# rev_m_v4.net
KiCad netlist of a schematic drawn in EAGLE
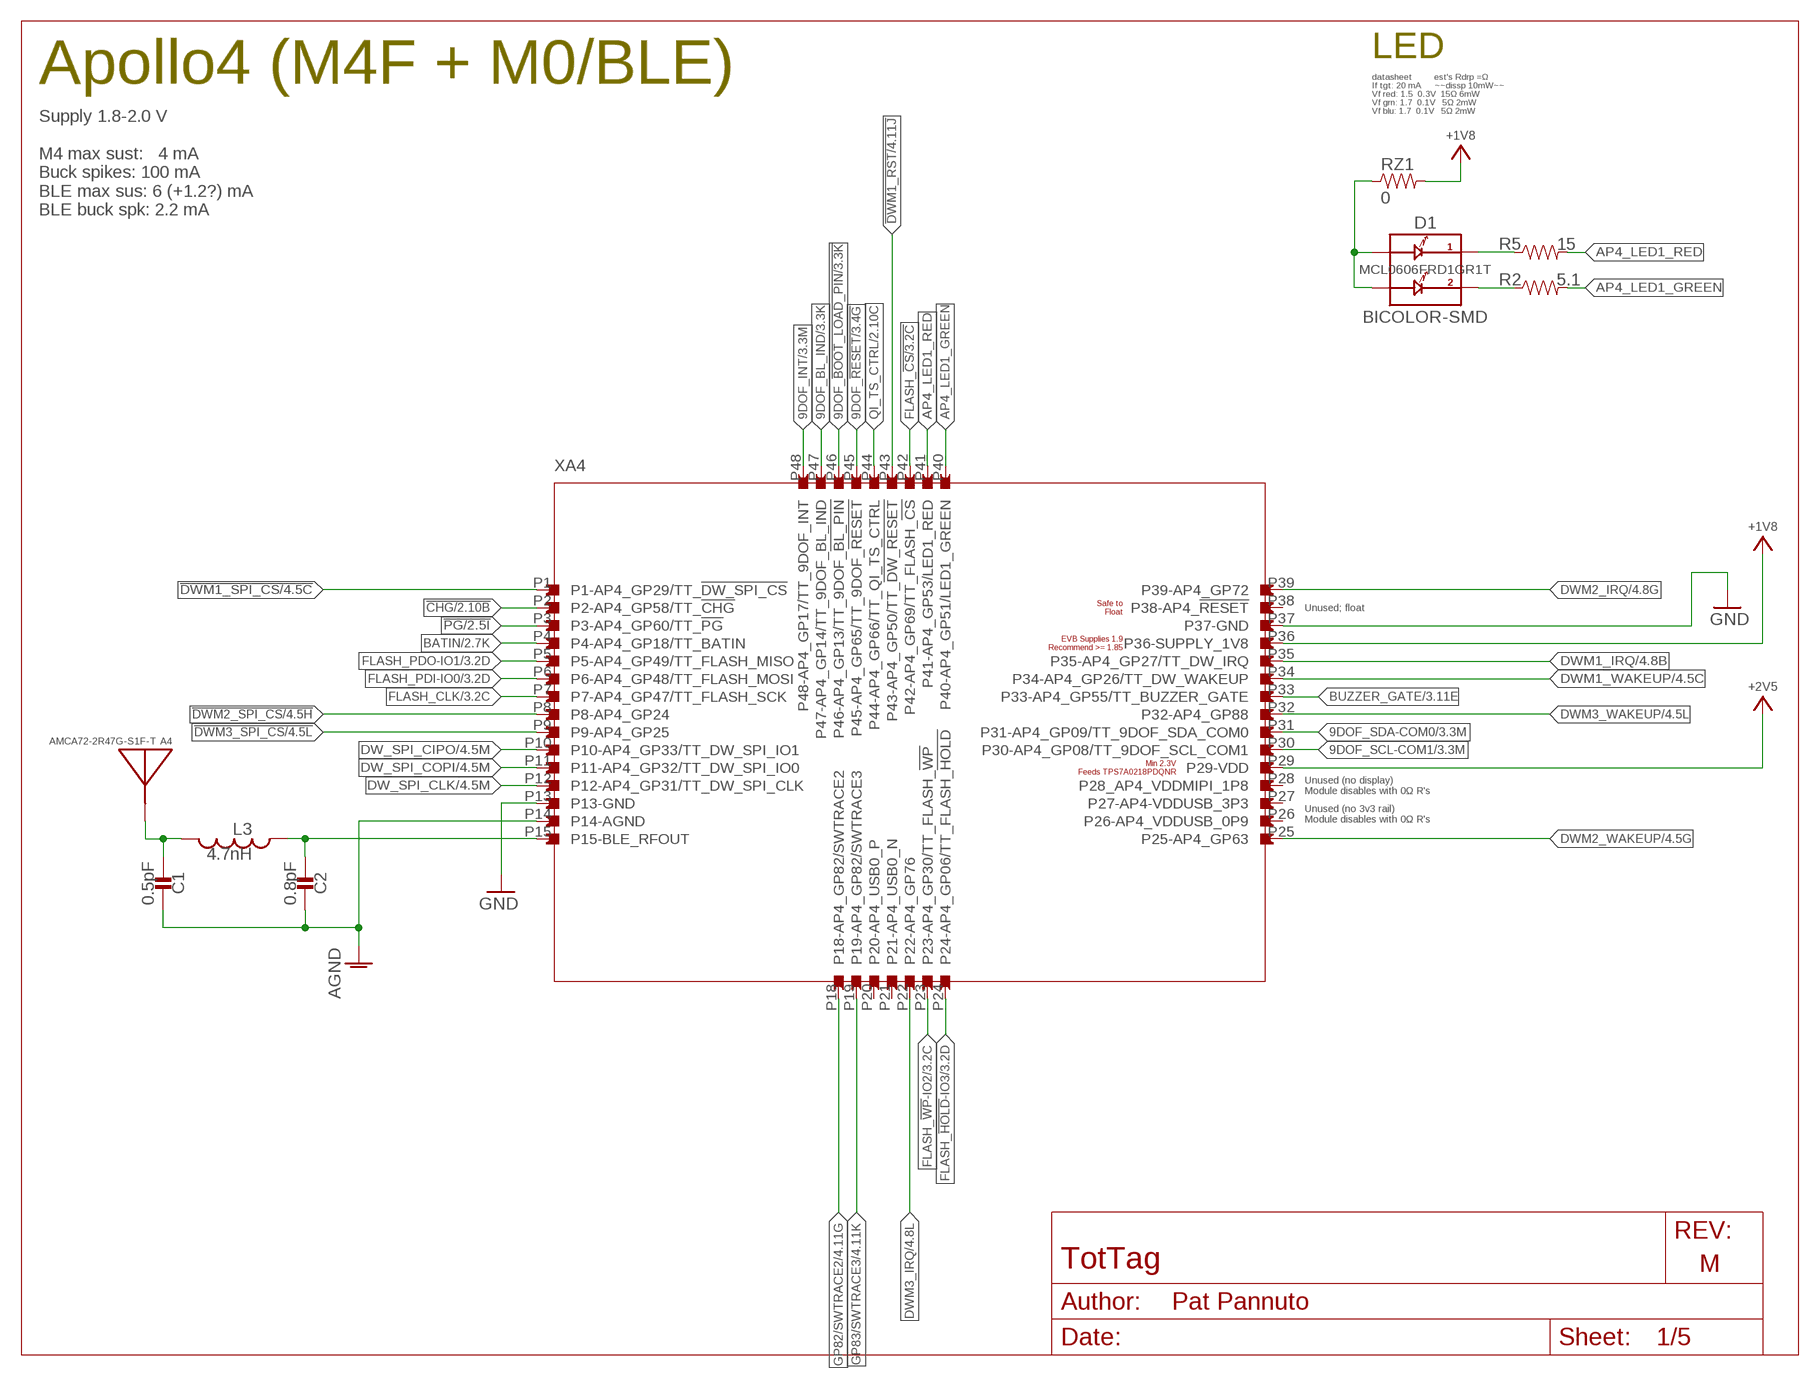
[diagram p0: schematic, sheet 1]
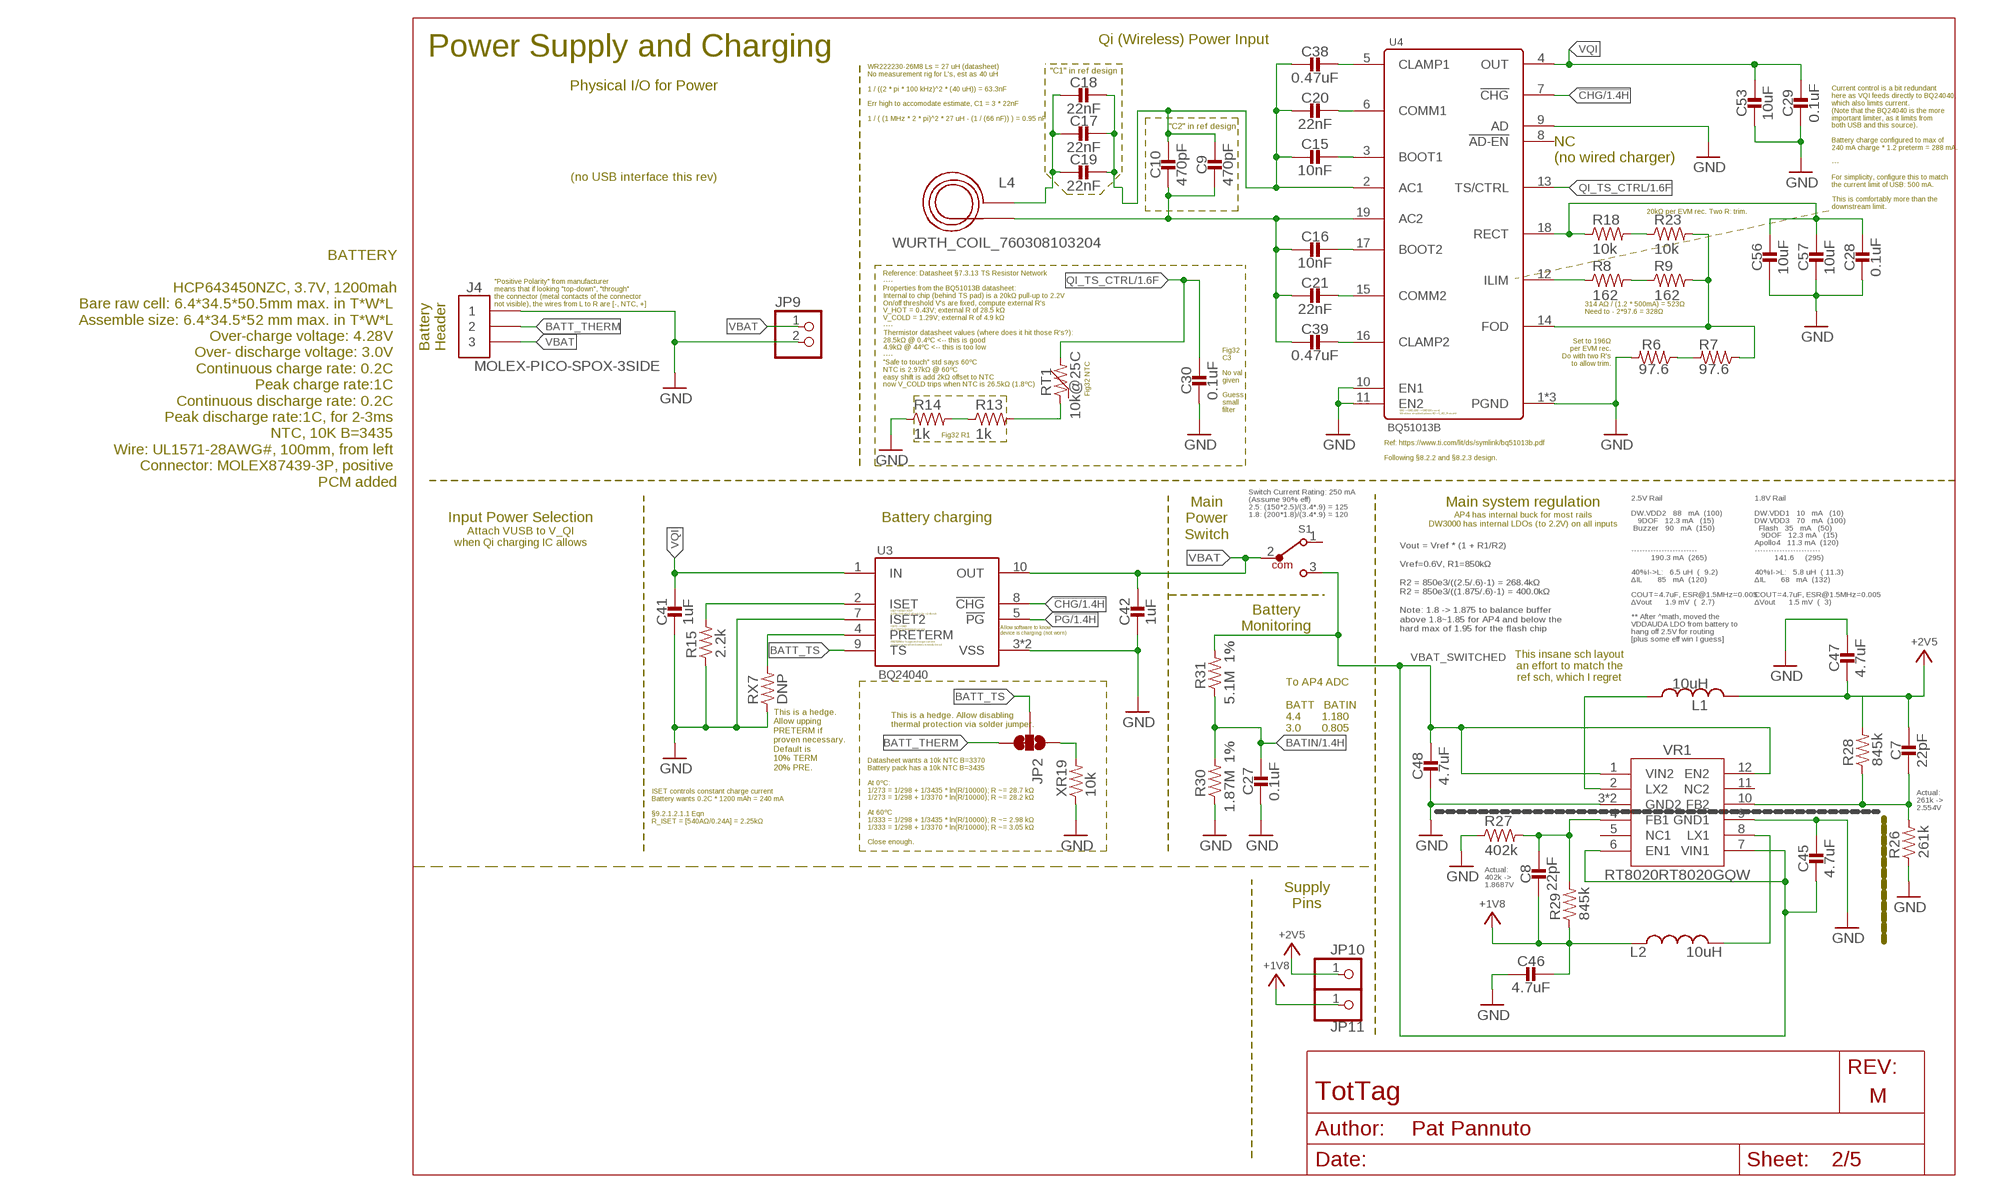
[diagram p1: schematic, sheet 2]
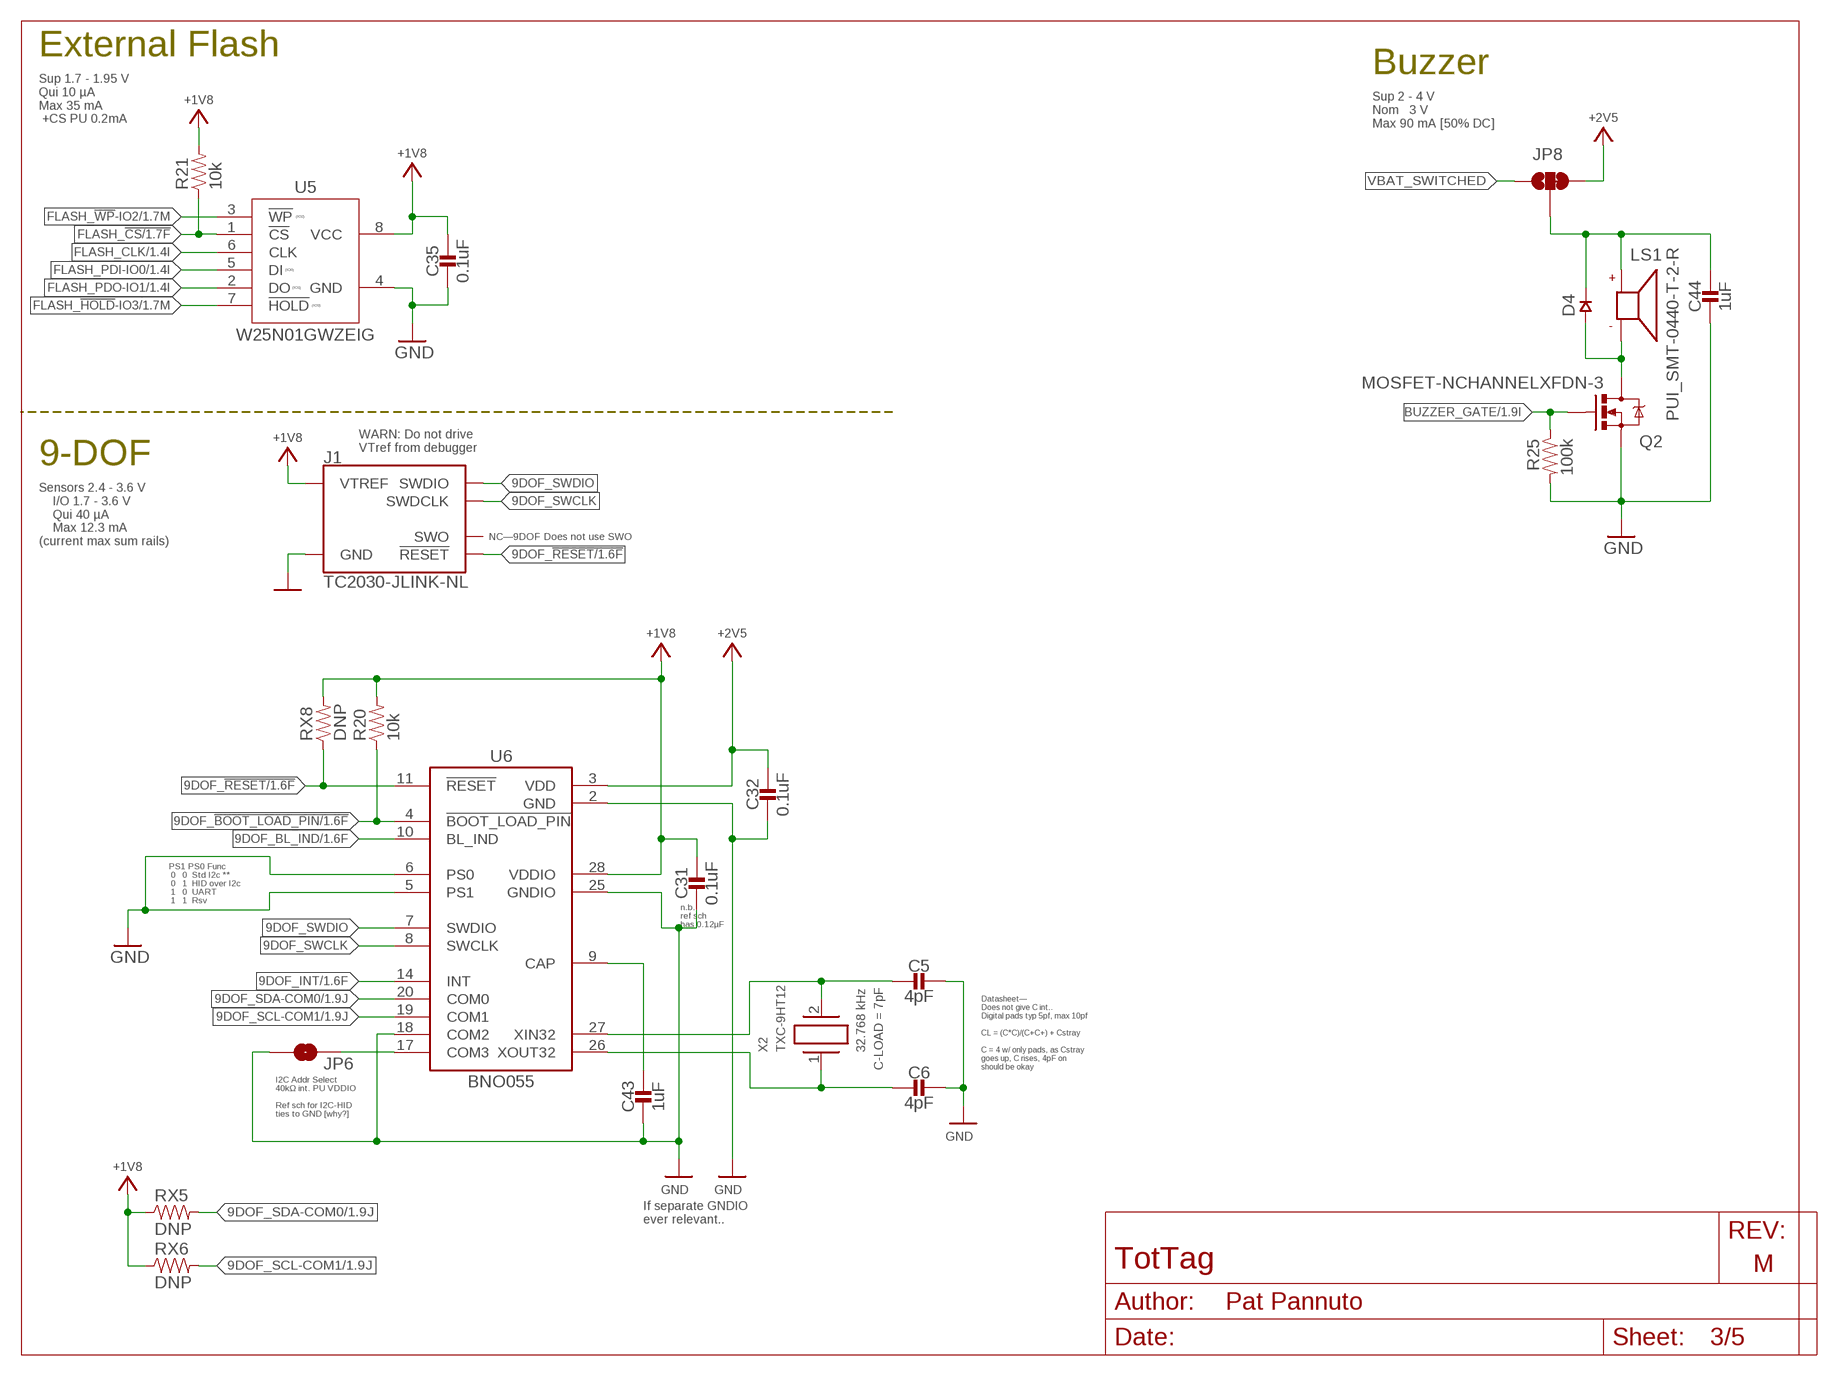
[diagram p2: schematic, sheet 3]
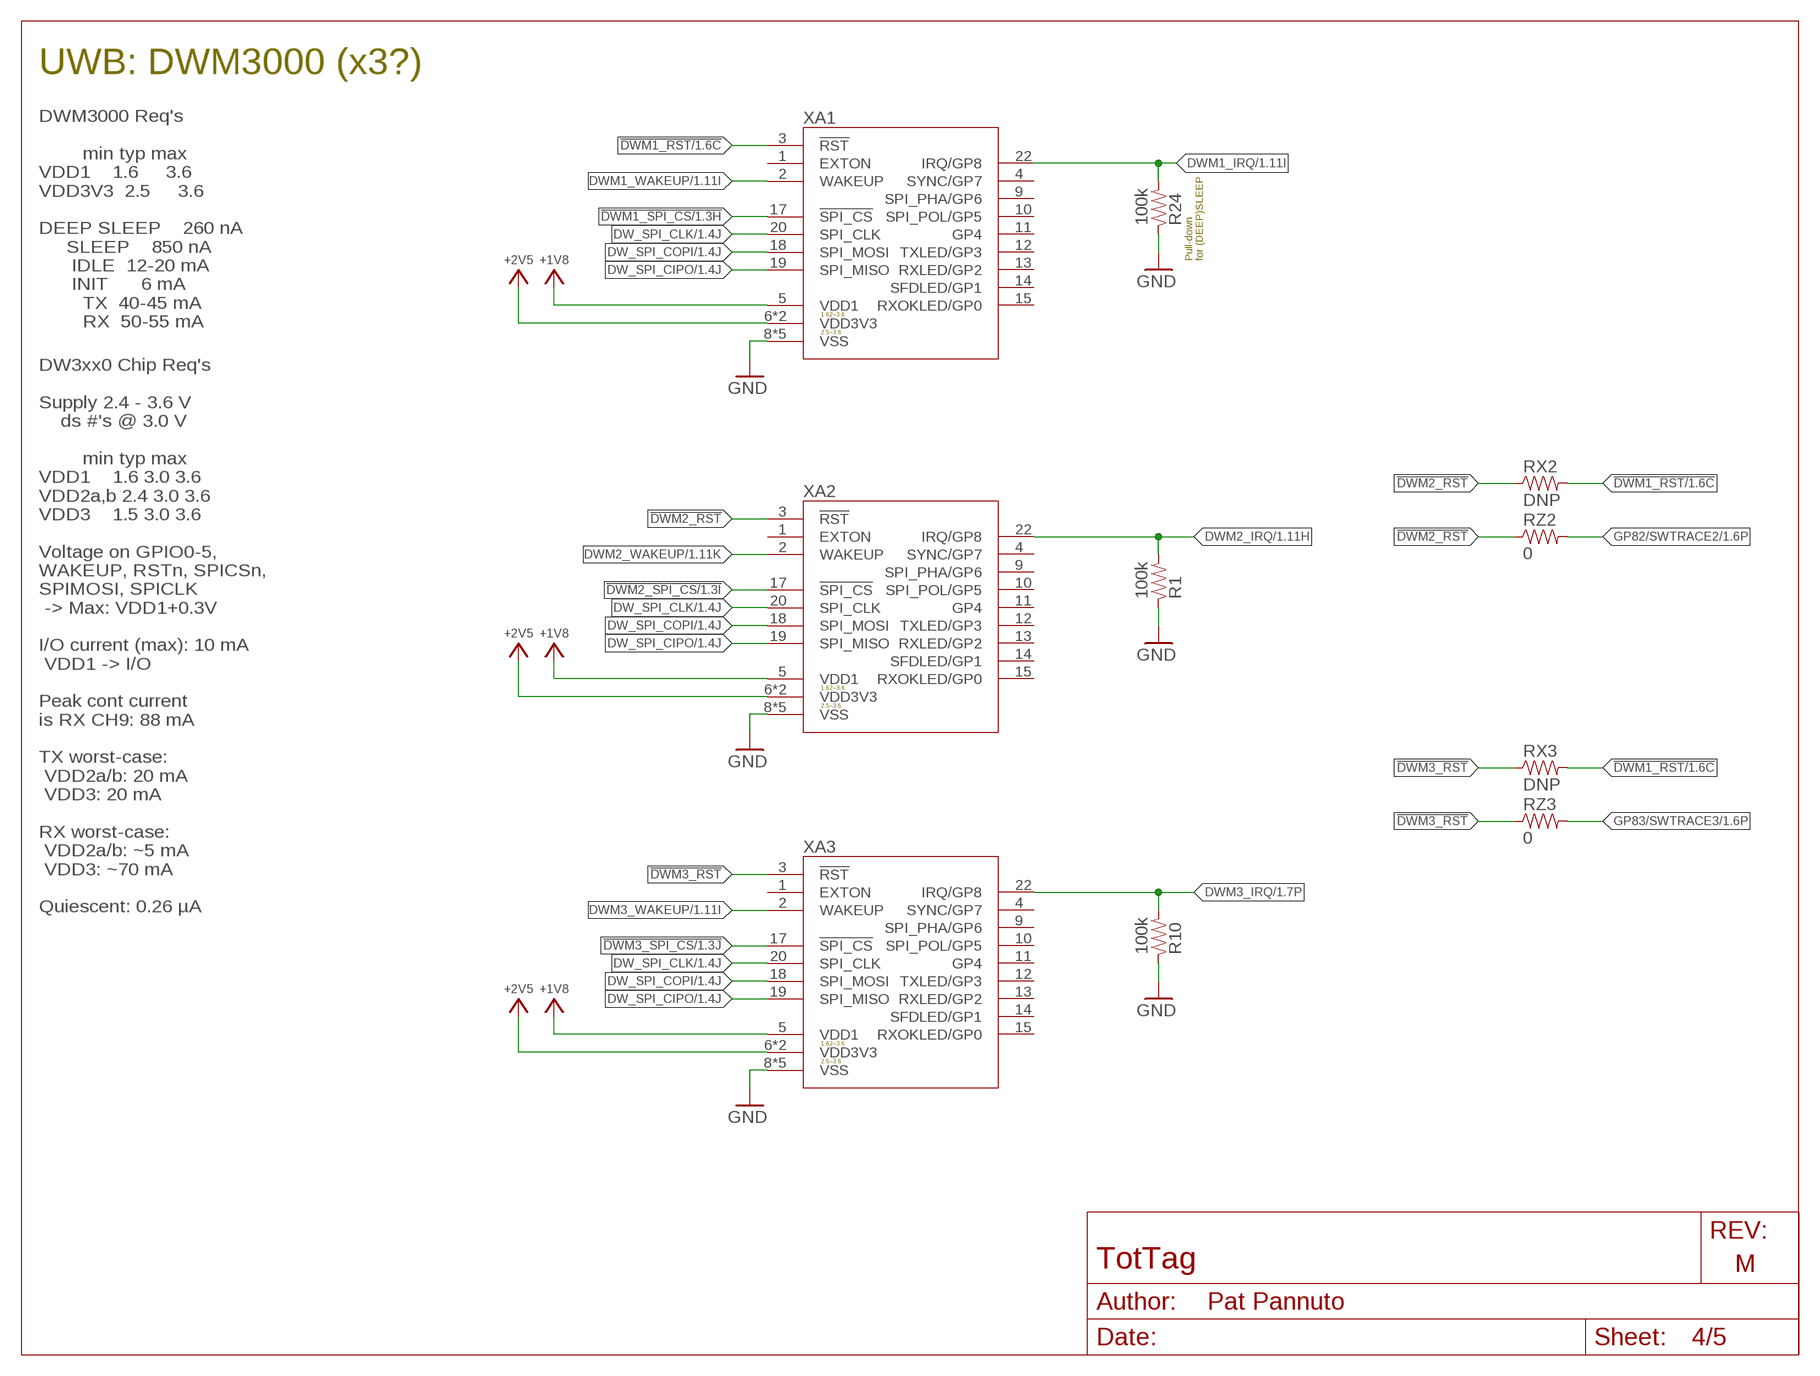
[diagram p3: schematic, sheet 4]
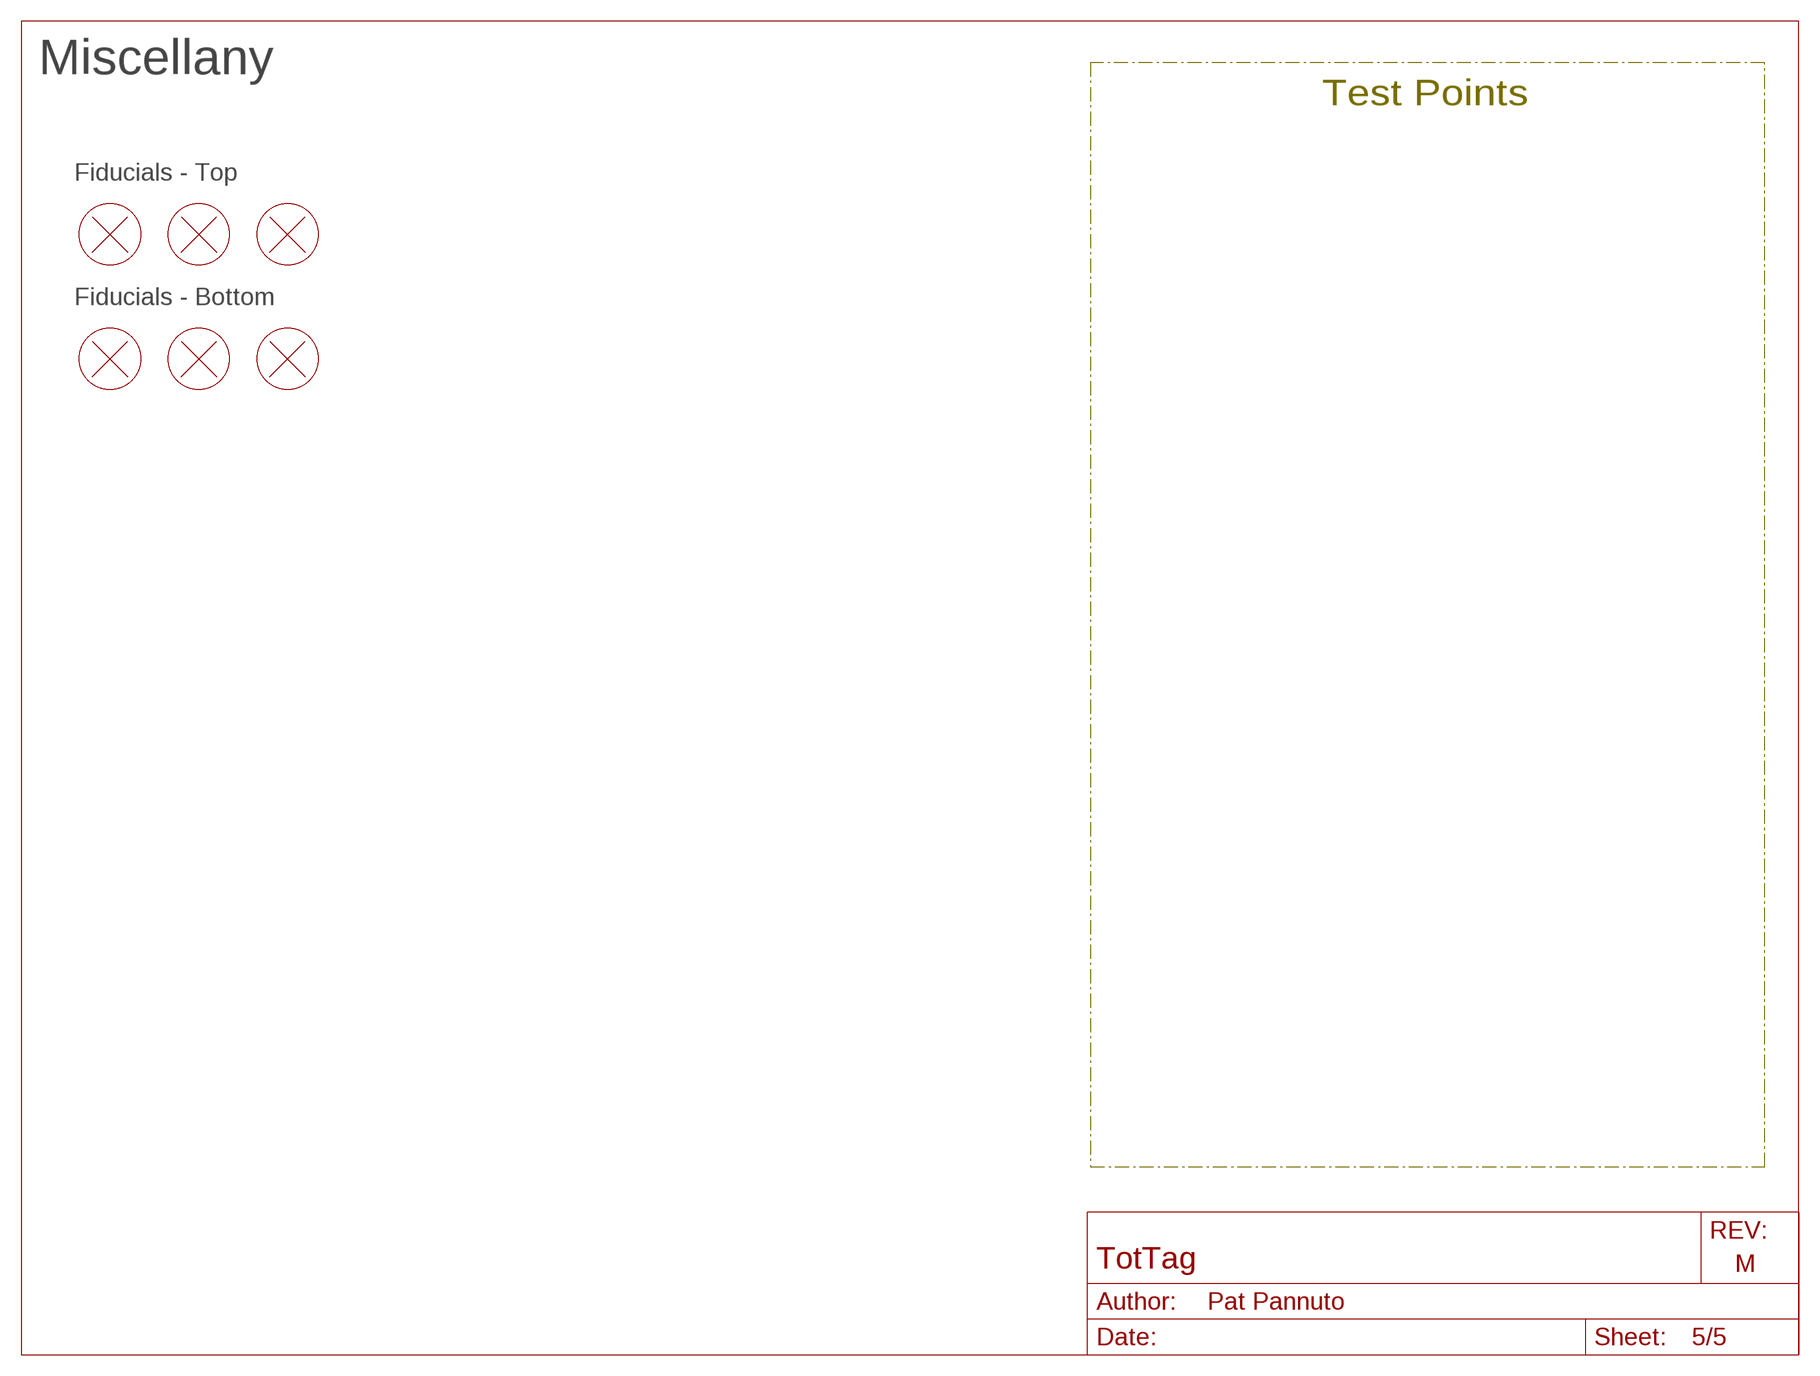
[diagram p4: schematic, sheet 5]

(export (version "E")
  (design (tool "Eeschema 10.0.6"))
  (components
    (comp (ref "A4")
      (value "AMCA72-2R47G-S1F-T")
      (footprint "eagle-import:AMCA72-2R470G-S1F-T")
      (fields (field (name "MPN") "AMCA72-2R470G-S1F-T4"))
      (libsource (lib "eagle-import") (part "AMCA72-2R47G-S1F-T"))
    )
    (comp (ref "C1")
      (value "0.5pF")
      (footprint "eagle-import:0402_CAP")
      (fields (field (name "MPN") "GJM1555C1HR50WB01D"))
      (libsource (lib "eagle-import") (part "CAPACITOR0402_CAP"))
    )
    (comp (ref "C2")
      (value "0.8pF")
      (footprint "eagle-import:0402_CAP")
      (fields (field (name "MPN") "GJM1555C1HR80WB01D"))
      (libsource (lib "eagle-import") (part "CAPACITOR0402_CAP"))
    )
    (comp (ref "D1")
      (value "BICOLOR-SMD")
      (footprint "eagle-import:LED-0606")
      (fields (field (name "MPN") "MCL0606FRD1GR1T"))
      (libsource (lib "eagle-import") (part "BICOLOR-SMD"))
    )
    (comp (ref "L3")
      (value "4.7nH")
      (footprint "eagle-import:0402_CAP")
      (fields (field (name "MPN") "LQW15AN4N7G8ZD"))
      (libsource (lib "eagle-import") (part "INDUCTOR0402"))
    )
    (comp (ref "R2")
      (value "5.1")
      (footprint "eagle-import:0402_RES")
      (fields (field (name "MPN") "RC0402JR-075R1L"))
      (libsource (lib "eagle-import") (part "RESISTOR0402_RES"))
    )
    (comp (ref "R5")
      (value "15")
      (footprint "eagle-import:0402_RES")
      (fields (field (name "MPN") "RC0402JR-0715RL"))
      (libsource (lib "eagle-import") (part "RESISTOR0402_RES"))
    )
    (comp (ref "RZ1")
      (value "0")
      (footprint "eagle-import:0603-RES")
      (fields (field (name "MPN") "RMCF0603ZT0R00"))
      (libsource (lib "eagle-import") (part "passives_20904581_RESISTOR0603_RES"))
    )
    (comp (ref "XA4")
      (value "APOLLO4_BLUEPLUS_MODULE")
      (footprint "eagle-import:APOLLO4_BLUEPLUS_MODULE")
      (libsource (lib "eagle-import") (part "APOLLO4_BLUEPLUS_MODULE"))
    )
    (comp (ref "C7")
      (value "22pF")
      (footprint "eagle-import:0201_CAP")
      (fields (field (name "MPN") "GRM0335C1H220FA01D"))
      (libsource (lib "eagle-import") (part "passives_20904581_CAPACITOR0201_CAP"))
    )
    (comp (ref "C8")
      (value "22pF")
      (footprint "eagle-import:0201_CAP")
      (fields (field (name "MPN") "GRM0335C1H220FA01D"))
      (libsource (lib "eagle-import") (part "passives_20904581_CAPACITOR0201_CAP"))
    )
    (comp (ref "C9")
      (value "470pF")
      (footprint "eagle-import:0402_CAP")
      (description "CAP CER 470PF 50V C0G/NP0 0402")
      (fields (field (name "MANUFACTURER") "Murata") (field (name "MPN") "GRM1555C1H471JA01J"))
      (libsource (lib "eagle-import") (part "passives_20904581_CAPACITOR0402_CAP"))
    )
    (comp (ref "C10")
      (value "470pF")
      (footprint "eagle-import:0402_CAP")
      (description "CAP CER 470PF 50V C0G/NP0 0402")
      (fields (field (name "MANUFACTURER") "Murata") (field (name "MPN") "GRM1555C1H471JA01J"))
      (libsource (lib "eagle-import") (part "passives_20904581_CAPACITOR0402_CAP"))
    )
    (comp (ref "C15")
      (value "10nF")
      (footprint "eagle-import:0402_CAP")
      (fields (field (name "MPN") "GRM155R71H103KA88J"))
      (libsource (lib "eagle-import") (part "passives_20904581_CAPACITOR0402_CAP"))
    )
    (comp (ref "C16")
      (value "10nF")
      (footprint "eagle-import:0402_CAP")
      (fields (field (name "MPN") "GRM155R71H103KA88J"))
      (libsource (lib "eagle-import") (part "passives_20904581_CAPACITOR0402_CAP"))
    )
    (comp (ref "C17")
      (value "22nF")
      (footprint "eagle-import:0402_CAP")
      (fields (field (name "MPN") "GRM155R71E223JA61D"))
      (libsource (lib "eagle-import") (part "passives_20904581_CAPACITOR0402_CAP"))
    )
    (comp (ref "C18")
      (value "22nF")
      (footprint "eagle-import:0402_CAP")
      (fields (field (name "MPN") "GRM155R71E223JA61D"))
      (libsource (lib "eagle-import") (part "passives_20904581_CAPACITOR0402_CAP"))
    )
    (comp (ref "C19")
      (value "22nF")
      (footprint "eagle-import:0402_CAP")
      (fields (field (name "MPN") "GRM155R71E223JA61D"))
      (libsource (lib "eagle-import") (part "passives_20904581_CAPACITOR0402_CAP"))
    )
    (comp (ref "C20")
      (value "22nF")
      (footprint "eagle-import:0402_CAP")
      (fields (field (name "MPN") "CC0402ZRY5V8BB223"))
      (libsource (lib "eagle-import") (part "passives_20904581_CAPACITOR0402_CAP"))
    )
    (comp (ref "C21")
      (value "22nF")
      (footprint "eagle-import:0402_CAP")
      (fields (field (name "MPN") "CC0402ZRY5V8BB223"))
      (libsource (lib "eagle-import") (part "passives_20904581_CAPACITOR0402_CAP"))
    )
    (comp (ref "C27")
      (value "0.1uF")
      (footprint "eagle-import:0402_CAP")
      (fields (field (name "MPN") "GRM155R71C104KA88J "))
      (libsource (lib "eagle-import") (part "CAPACITOR0402_CAP"))
    )
    (comp (ref "C28")
      (value "0.1uF")
      (footprint "eagle-import:0402_CAP")
      (fields (field (name "MPN") "GRM155R71C104KA88J "))
      (libsource (lib "eagle-import") (part "CAPACITOR0402_CAP"))
    )
    (comp (ref "C29")
      (value "0.1uF")
      (footprint "eagle-import:0402_CAP")
      (fields (field (name "MPN") "GRM155R71C104KA88J "))
      (libsource (lib "eagle-import") (part "CAPACITOR0402_CAP"))
    )
    (comp (ref "C30")
      (value "0.1uF")
      (footprint "eagle-import:0402_CAP")
      (fields (field (name "MPN") "GRM155R71C104KA88J "))
      (libsource (lib "eagle-import") (part "CAPACITOR0402_CAP"))
    )
    (comp (ref "C38")
      (value "0.47uF")
      (footprint "eagle-import:0402_CAP")
      (fields (field (name "MPN") "GRT155R61E474ME01D"))
      (libsource (lib "eagle-import") (part "passives_20904581_CAPACITOR0402_CAP"))
    )
    (comp (ref "C39")
      (value "0.47uF")
      (footprint "eagle-import:0402_CAP")
      (fields (field (name "MPN") "GRT155R61E474ME01D"))
      (libsource (lib "eagle-import") (part "passives_20904581_CAPACITOR0402_CAP"))
    )
    (comp (ref "C41")
      (value "1uF")
      (footprint "eagle-import:0402_CAP")
      (fields (field (name "MPN") "GRM155R70J105KA12J"))
      (libsource (lib "eagle-import") (part "CAPACITOR0402_CAP"))
    )
    (comp (ref "C42")
      (value "1uF")
      (footprint "eagle-import:0402_CAP")
      (fields (field (name "MPN") "GRM155R70J105KA12J"))
      (libsource (lib "eagle-import") (part "CAPACITOR0402_CAP"))
    )
    (comp (ref "C45")
      (value "4.7uF")
      (footprint "eagle-import:0603_CAP")
      (fields (field (name "MPN") "C1608X7S1A475K080AC"))
      (libsource (lib "eagle-import") (part "passives_20904581_CAPACITOR0603_CAP"))
    )
    (comp (ref "C46")
      (value "4.7uF")
      (footprint "eagle-import:0603_CAP")
      (fields (field (name "MPN") "C1608X7S1A475K080AC"))
      (libsource (lib "eagle-import") (part "passives_20904581_CAPACITOR0603_CAP"))
    )
    (comp (ref "C47")
      (value "4.7uF")
      (footprint "eagle-import:0603_CAP")
      (fields (field (name "MPN") "C1608X7S1A475K080AC"))
      (libsource (lib "eagle-import") (part "passives_20904581_CAPACITOR0603_CAP"))
    )
    (comp (ref "C48")
      (value "4.7uF")
      (footprint "eagle-import:0603_CAP")
      (fields (field (name "MPN") "C1608X7S1A475K080AC"))
      (libsource (lib "eagle-import") (part "passives_20904581_CAPACITOR0603_CAP"))
    )
    (comp (ref "C53")
      (value "10uF")
      (footprint "eagle-import:0603_CAP")
      (fields (field (name "MPN") "CM105X5R106M25AT"))
      (libsource (lib "eagle-import") (part "passives_20904581_CAPACITOR0603_CAP"))
    )
    (comp (ref "C56")
      (value "10uF")
      (footprint "eagle-import:0603_CAP")
      (fields (field (name "MPN") "CM105X5R106M25AT"))
      (libsource (lib "eagle-import") (part "passives_20904581_CAPACITOR0603_CAP"))
    )
    (comp (ref "C57")
      (value "10uF")
      (footprint "eagle-import:0603_CAP")
      (fields (field (name "MPN") "CM105X5R106M25AT"))
      (libsource (lib "eagle-import") (part "passives_20904581_CAPACITOR0603_CAP"))
    )
    (comp (ref "J4")
      (value "MOLEX-PICO-SPOX-3SIDE")
      (footprint "eagle-import:MOLEX-PICO-SPOX-3_SIDE")
      (libsource (lib "eagle-import") (part "MOLEX-PICO-SPOX-3SIDE"))
    )
    (comp (ref "JP2")
      (value "JUMPER-SMT_3_1-NC_TRACE_SILK")
      (footprint "eagle-import:SMT-JUMPER_3_1-NC_TRACE_SILK")
      (libsource (lib "eagle-import") (part "JUMPER-SMT_3_1-NC_TRACE_SILK"))
    )
    (comp (ref "JP9")
      (value "PINHD-1X2")
      (footprint "eagle-import:1X02")
      (libsource (lib "eagle-import") (part "PINHD-1X2"))
    )
    (comp (ref "JP10")
      (value "PINHD-1X1")
      (footprint "eagle-import:1X01")
      (libsource (lib "eagle-import") (part "PINHD-1X1"))
    )
    (comp (ref "JP11")
      (value "PINHD-1X1")
      (footprint "eagle-import:1X01")
      (libsource (lib "eagle-import") (part "PINHD-1X1"))
    )
    (comp (ref "L1")
      (value "10uH")
      (footprint "eagle-import:NRX3015")
      (fields (field (name "MANUFACTURER") "TAIYO YUDEN") (field (name "MPN") "NR3015T100M"))
      (libsource (lib "eagle-import") (part "INDUCTORNRX3015"))
    )
    (comp (ref "L2")
      (value "10uH")
      (footprint "eagle-import:NRX3015")
      (fields (field (name "MANUFACTURER") "TAIYO YUDEN") (field (name "MPN") "NR3015T100M"))
      (libsource (lib "eagle-import") (part "INDUCTORNRX3015"))
    )
    (comp (ref "L4")
      (value "WURTH_COIL_760308103204")
      (footprint "eagle-import:WURTH_COIL_760308103204")
      (fields (field (name "MANUFACTURER") "Würth Elektronik") (field (name "MPN") "760308103204"))
      (libsource (lib "eagle-import") (part "WURTH_COIL_760308103204"))
    )
    (comp (ref "R6")
      (value "97.6")
      (footprint "eagle-import:0402_RES")
      (fields (field (name "MPN") "RMCF0402FT97R6"))
      (libsource (lib "eagle-import") (part "passives_20904581_RESISTOR0402_RES"))
    )
    (comp (ref "R7")
      (value "97.6")
      (footprint "eagle-import:0402_RES")
      (fields (field (name "MPN") "RMCF0402FT97R6"))
      (libsource (lib "eagle-import") (part "passives_20904581_RESISTOR0402_RES"))
    )
    (comp (ref "R8")
      (value "162")
      (footprint "eagle-import:0402_RES")
      (fields (field (name "MPN") "RMCF0402FT162R"))
      (libsource (lib "eagle-import") (part "passives_20904581_RESISTOR0402_RES"))
    )
    (comp (ref "R9")
      (value "162")
      (footprint "eagle-import:0402_RES")
      (fields (field (name "MPN") "RMCF0402FT162R"))
      (libsource (lib "eagle-import") (part "passives_20904581_RESISTOR0402_RES"))
    )
    (comp (ref "R13")
      (value "1k")
      (footprint "eagle-import:0402_RES")
      (libsource (lib "eagle-import") (part "RESISTOR0402_RES"))
    )
    (comp (ref "R14")
      (value "1k")
      (footprint "eagle-import:0402_RES")
      (libsource (lib "eagle-import") (part "RESISTOR0402_RES"))
    )
    (comp (ref "R15")
      (value "2.2k")
      (footprint "eagle-import:0402_RES")
      (fields (field (name "MPN") "RMCF0402JT2K20"))
      (libsource (lib "eagle-import") (part "passives_20904581_RESISTOR0402_RES"))
    )
    (comp (ref "R18")
      (value "10k")
      (footprint "eagle-import:0402_RES")
      (fields (field (name "MPN") "RC0402JR-0710KL"))
      (libsource (lib "eagle-import") (part "RESISTOR0402_RES"))
    )
    (comp (ref "R23")
      (value "10k")
      (footprint "eagle-import:0402_RES")
      (fields (field (name "MPN") "RC0402JR-0710KL"))
      (libsource (lib "eagle-import") (part "RESISTOR0402_RES"))
    )
    (comp (ref "R26")
      (value "261k")
      (footprint "eagle-import:0201_RES")
      (fields (field (name "MPN") "ERJ-1GNF2613C"))
      (libsource (lib "eagle-import") (part "passives_20904581_RESISTOR0201_RES"))
    )
    (comp (ref "R27")
      (value "402k")
      (footprint "eagle-import:0201_RES")
      (fields (field (name "MPN") "ERJ-1GNF4023C"))
      (libsource (lib "eagle-import") (part "passives_20904581_RESISTOR0201_RES"))
    )
    (comp (ref "R28")
      (value "845k")
      (footprint "eagle-import:0201_RES")
      (fields (field (name "MPN") "ERJ-1GNF8453C"))
      (libsource (lib "eagle-import") (part "passives_20904581_RESISTOR0201_RES"))
    )
    (comp (ref "R29")
      (value "845k")
      (footprint "eagle-import:0201_RES")
      (fields (field (name "MPN") "ERJ-1GNF8453C"))
      (libsource (lib "eagle-import") (part "passives_20904581_RESISTOR0201_RES"))
    )
    (comp (ref "R30")
      (value "1.87M")
      (footprint "eagle-import:0402_RES")
      (fields (field (name "MPN") "RMCF0402FT1M87") (field (name "TOLERANCE") "1%"))
      (libsource (lib "eagle-import") (part "RESISTOR0402_RES"))
    )
    (comp (ref "R31")
      (value "5.1M")
      (footprint "eagle-import:0402_RES")
      (fields (field (name "MPN") "RMCF0402FT5M10") (field (name "TOLERANCE") "1%"))
      (libsource (lib "eagle-import") (part "RESISTOR0402_RES"))
    )
    (comp (ref "RT1")
      (value "10k@25C")
      (footprint "eagle-import:0402_RES")
      (fields (field (name "MPN") "NCU15XH103F60RC"))
      (libsource (lib "eagle-import") (part "THERMISTOR0402"))
    )
    (comp (ref "RX7")
      (value "DNP")
      (footprint "eagle-import:0402_RES")
      (libsource (lib "eagle-import") (part "passives_20904581_RESISTOR0402_RES"))
    )
    (comp (ref "S1")
      (value "450404015514")
      (footprint "eagle-import:450404015514")
      (libsource (lib "eagle-import") (part "450404015514"))
    )
    (comp (ref "U3")
      (value "BQ24040")
      (footprint "eagle-import:DSQ0010A")
      (fields (field (name "MPN") "BQ24040DSQR"))
      (libsource (lib "eagle-import") (part "BQ24040"))
    )
    (comp (ref "U4")
      (value "BQ51013B")
      (footprint "eagle-import:RHL0020A")
      (fields (field (name "MPN") "BQ51013BRHLR"))
      (libsource (lib "eagle-import") (part "BQ51013B"))
    )
    (comp (ref "VR1")
      (value "RT8020RT8020GQW")
      (footprint "eagle-import:SON45P300X300X80-13T160X250N")
      (fields (field (name "MANUFACTURER") "RichTek") (field (name "MPN") "RT8020GQW"))
      (libsource (lib "eagle-import") (part "RT8020RT8020GQW"))
    )
    (comp (ref "XR19")
      (value "10k")
      (footprint "eagle-import:0402_RES")
      (fields (field (name "MPN") "RC0402JR-0710KL"))
      (libsource (lib "eagle-import") (part "RESISTOR0402_RES"))
    )
    (comp (ref "FD1")
      (value "FIDUCIAL")
      (footprint "eagle-import:FIDUCIAL_1MM-CU_2MM-MASK")
      (libsource (lib "eagle-import") (part "FIDUCIAL"))
    )
    (comp (ref "FD2")
      (value "FIDUCIAL")
      (footprint "eagle-import:FIDUCIAL_1MM-CU_2MM-MASK")
      (libsource (lib "eagle-import") (part "FIDUCIAL"))
    )
    (comp (ref "FD3")
      (value "FIDUCIAL")
      (footprint "eagle-import:FIDUCIAL_1MM-CU_2MM-MASK")
      (libsource (lib "eagle-import") (part "FIDUCIAL"))
    )
    (comp (ref "FD4")
      (value "FIDUCIAL")
      (footprint "eagle-import:FIDUCIAL_1MM-CU_2MM-MASK")
      (libsource (lib "eagle-import") (part "FIDUCIAL"))
    )
    (comp (ref "FD5")
      (value "FIDUCIAL")
      (footprint "eagle-import:FIDUCIAL_1MM-CU_2MM-MASK")
      (libsource (lib "eagle-import") (part "FIDUCIAL"))
    )
    (comp (ref "FD6")
      (value "FIDUCIAL")
      (footprint "eagle-import:FIDUCIAL_1MM-CU_2MM-MASK")
      (libsource (lib "eagle-import") (part "FIDUCIAL"))
    )
    (comp (ref "R1")
      (value "100k")
      (footprint "eagle-import:0402_RES")
      (fields (field (name "MPN") "RT0402BRE07100KL"))
      (libsource (lib "eagle-import") (part "RESISTOR0402_RES"))
    )
    (comp (ref "R10")
      (value "100k")
      (footprint "eagle-import:0402_RES")
      (fields (field (name "MPN") "RT0402BRE07100KL"))
      (libsource (lib "eagle-import") (part "RESISTOR0402_RES"))
    )
    (comp (ref "R24")
      (value "100k")
      (footprint "eagle-import:0402_RES")
      (fields (field (name "MPN") "RT0402BRE07100KL"))
      (libsource (lib "eagle-import") (part "RESISTOR0402_RES"))
    )
    (comp (ref "RX2")
      (value "DNP")
      (footprint "eagle-import:0603-RES")
      (libsource (lib "eagle-import") (part "passives_20904581_RESISTOR0603_RES"))
    )
    (comp (ref "RX3")
      (value "DNP")
      (footprint "eagle-import:0603-RES")
      (libsource (lib "eagle-import") (part "passives_20904581_RESISTOR0603_RES"))
    )
    (comp (ref "RZ2")
      (value "0")
      (footprint "eagle-import:0603-RES")
      (fields (field (name "MPN") "RMCF0603ZT0R00"))
      (libsource (lib "eagle-import") (part "passives_20904581_RESISTOR0603_RES"))
    )
    (comp (ref "RZ3")
      (value "0")
      (footprint "eagle-import:0603-RES")
      (fields (field (name "MPN") "RMCF0603ZT0R00"))
      (libsource (lib "eagle-import") (part "passives_20904581_RESISTOR0603_RES"))
    )
    (comp (ref "XA1")
      (value "DWM3000")
      (footprint "eagle-import:DWM3000")
      (libsource (lib "eagle-import") (part "DWM3000"))
    )
    (comp (ref "XA2")
      (value "DWM3000")
      (footprint "eagle-import:DWM3000")
      (libsource (lib "eagle-import") (part "DWM3000"))
    )
    (comp (ref "XA3")
      (value "DWM3000")
      (footprint "eagle-import:DWM3000")
      (libsource (lib "eagle-import") (part "DWM3000"))
    )
    (comp (ref "C5")
      (value "4pF")
      (footprint "eagle-import:0201_CAP")
      (fields (field (name "MANUFACTURER") "Murata") (field (name "MPN") "GRM0335C1H4R0BA01D"))
      (libsource (lib "eagle-import") (part "passives_20904581_CAPACITOR0201_CAP"))
    )
    (comp (ref "C6")
      (value "4pF")
      (footprint "eagle-import:0201_CAP")
      (fields (field (name "MANUFACTURER") "Murata") (field (name "MPN") "GRM0335C1H4R0BA01D"))
      (libsource (lib "eagle-import") (part "passives_20904581_CAPACITOR0201_CAP"))
    )
    (comp (ref "C31")
      (value "0.1uF")
      (footprint "eagle-import:0402_CAP")
      (fields (field (name "MPN") "CL05A104KP5NNNC"))
      (libsource (lib "eagle-import") (part "passives_20904581_CAPACITOR0402_CAP"))
    )
    (comp (ref "C32")
      (value "0.1uF")
      (footprint "eagle-import:0402_CAP")
      (fields (field (name "MPN") "CL05A104KP5NNNC"))
      (libsource (lib "eagle-import") (part "passives_20904581_CAPACITOR0402_CAP"))
    )
    (comp (ref "C35")
      (value "0.1uF")
      (footprint "eagle-import:0402_CAP")
      (fields (field (name "MPN") "CL05A104KP5NNNC"))
      (libsource (lib "eagle-import") (part "passives_20904581_CAPACITOR0402_CAP"))
    )
    (comp (ref "C43")
      (value "1uF")
      (footprint "eagle-import:0402_CAP")
      (fields (field (name "MPN") "GRM155R70J105KA12J"))
      (libsource (lib "eagle-import") (part "CAPACITOR0402_CAP"))
    )
    (comp (ref "C44")
      (value "1uF")
      (footprint "eagle-import:0402_CAP")
      (fields (field (name "MPN") "GRM155R70J105KA12J"))
      (libsource (lib "eagle-import") (part "CAPACITOR0402_CAP"))
    )
    (comp (ref "D4")
      (value "DIODE0402")
      (footprint "eagle-import:0402_DIODE")
      (fields (field (name "MPN") "CDSQR400B-HF"))
      (libsource (lib "eagle-import") (part "DIODE0402"))
    )
    (comp (ref "J1")
      (value "TC2030-JLINK-NL")
      (footprint "eagle-import:TC2030-IDC-NL")
      (libsource (lib "eagle-import") (part "TC2030-JLINK-NL"))
    )
    (comp (ref "JP6")
      (value "JUMPER-SMT_2_NO_SILK")
      (footprint "eagle-import:SMT-JUMPER_2_NO_SILK")
      (libsource (lib "eagle-import") (part "JUMPER-SMT_2_NO_SILK"))
    )
    (comp (ref "JP8")
      (value "JUMPER-SMT_3_1-NC_TRACE_SILK")
      (footprint "eagle-import:SMT-JUMPER_3_1-NC_TRACE_SILK")
      (libsource (lib "eagle-import") (part "JUMPER-SMT_3_1-NC_TRACE_SILK"))
    )
    (comp (ref "LS1")
      (value "PUI_SMT-0440-T-2-R")
      (footprint "eagle-import:SMT-0440-T-2-R")
      (fields (field (name "MPN") "SMT-0440-T-2-R"))
      (libsource (lib "eagle-import") (part "PUI_SMT-0440-T-2-R"))
    )
    (comp (ref "Q2")
      (value "MOSFET-NCHANNELXFDN-3")
      (footprint "eagle-import:XFDFN-3")
      (libsource (lib "eagle-import") (part "MOSFET-NCHANNELXFDN-3"))
    )
    (comp (ref "R20")
      (value "10k")
      (footprint "eagle-import:0402_RES")
      (fields (field (name "MPN") "RC0402JR-0710KL"))
      (libsource (lib "eagle-import") (part "RESISTOR0402_RES"))
    )
    (comp (ref "R21")
      (value "10k")
      (footprint "eagle-import:0402_RES")
      (fields (field (name "MPN") "RC0402JR-0710KL"))
      (libsource (lib "eagle-import") (part "RESISTOR0402_RES"))
    )
    (comp (ref "R25")
      (value "100k")
      (footprint "eagle-import:0402_RES")
      (fields (field (name "MPN") "RT0402BRE07100KL"))
      (libsource (lib "eagle-import") (part "RESISTOR0402_RES"))
    )
    (comp (ref "RX5")
      (value "DNP")
      (footprint "eagle-import:0603-RES")
      (libsource (lib "eagle-import") (part "passives_20904581_RESISTOR0603_RES"))
    )
    (comp (ref "RX6")
      (value "DNP")
      (footprint "eagle-import:0603-RES")
      (libsource (lib "eagle-import") (part "passives_20904581_RESISTOR0603_RES"))
    )
    (comp (ref "RX8")
      (value "DNP")
      (footprint "eagle-import:0603-RES")
      (libsource (lib "eagle-import") (part "passives_20904581_RESISTOR0603_RES"))
    )
    (comp (ref "U5")
      (value "W25N01GWZEIG")
      (footprint "eagle-import:WSON127P800X600X80-9T430X340N")
      (fields (field (name "MANUFACTURER") "Winbond"))
      (libsource (lib "eagle-import") (part "W25N01GWZEIG"))
    )
    (comp (ref "U6")
      (value "BNO055")
      (footprint "eagle-import:LGA28R0P510X4_5P2X3P8X1")
      (fields (field (name "MANUFACTURER") "Bosch Scientific"))
      (libsource (lib "eagle-import") (part "BNO055"))
    )
    (comp (ref "X2")
      (value "TXC-9HT12")
      (footprint "eagle-import:TXC-9HT12")
      (fields
        (field (name "C-LOAD") "7pF")
        (field (name "FREQUENCY") "32.768 kHz")
        (field (name "MANUFACTURER") "TXC Corp")
        (field (name "MPN") "9HT12-32.768KDZY-T")
      )
      (libsource (lib "eagle-import") (part "TXC-9HT12"))
    )
  )
  (nets
    (net (code "1") (name "+1V8") (class "Default")
      (node (ref "C31") (pin "1") (pinfunction "1_1") (pintype "bidirectional"))
      (node (ref "C35") (pin "1") (pinfunction "1_1") (pintype "bidirectional"))
      (node (ref "C46") (pin "1") (pinfunction "1_1") (pintype "bidirectional"))
      (node (ref "C8") (pin "P$2") (pinfunction "2_P$2") (pintype "bidirectional"))
      (node (ref "J1") (pin "1") (pinfunction "VTREF_1") (pintype "bidirectional"))
      (node (ref "JP11") (pin "1") (pinfunction "1_1") (pintype "passive"))
      (node (ref "L2") (pin "P$1") (pinfunction "1_P$1") (pintype "bidirectional"))
      (node (ref "R20") (pin "2") (pinfunction "2_2") (pintype "passive"))
      (node (ref "R21") (pin "2") (pinfunction "2_2") (pintype "passive"))
      (node (ref "R29") (pin "1") (pinfunction "1_1") (pintype "passive"))
      (node (ref "RX5") (pin "1") (pinfunction "1_1") (pintype "passive"))
      (node (ref "RX6") (pin "1") (pinfunction "1_1") (pintype "passive"))
      (node (ref "RX8") (pin "2") (pinfunction "2_2") (pintype "passive"))
      (node (ref "RZ1") (pin "2") (pinfunction "2_2") (pintype "passive"))
      (node (ref "U5") (pin "8") (pinfunction "VCC_8") (pintype "bidirectional"))
      (node (ref "U6") (pin "28") (pinfunction "VDDIO_28") (pintype "bidirectional"))
      (node (ref "XA1") (pin "5") (pinfunction "VDD1_5") (pintype "bidirectional"))
      (node (ref "XA2") (pin "5") (pinfunction "VDD1_5") (pintype "bidirectional"))
      (node (ref "XA3") (pin "5") (pinfunction "VDD1_5") (pintype "bidirectional"))
      (node (ref "XA4") (pin "P36") (pinfunction "P36-SUPPLY_1V8_P36") (pintype "bidirectional"))
    )
    (net (code "2") (name "+2V5") (class "Default")
      (node (ref "C32") (pin "1") (pinfunction "1_1") (pintype "bidirectional"))
      (node (ref "C47") (pin "2") (pinfunction "2_2") (pintype "bidirectional"))
      (node (ref "C7") (pin "P$1") (pinfunction "1_P$1") (pintype "bidirectional"))
      (node (ref "JP10") (pin "1") (pinfunction "1_1") (pintype "passive"))
      (node (ref "JP8") (pin "3") (pinfunction "3_3") (pintype "passive"))
      (node (ref "L1") (pin "P$2") (pinfunction "2_P$2") (pintype "bidirectional"))
      (node (ref "R28") (pin "2") (pinfunction "2_2") (pintype "passive"))
      (node (ref "U6") (pin "3") (pinfunction "VDD_3") (pintype "bidirectional"))
      (node (ref "XA1") (pin "6") (pinfunction "VDD3V3_6") (pintype "bidirectional"))
      (node (ref "XA1") (pin "7") (pinfunction "VDD3V3_7") (pintype "bidirectional"))
      (node (ref "XA2") (pin "6") (pinfunction "VDD3V3_6") (pintype "bidirectional"))
      (node (ref "XA2") (pin "7") (pinfunction "VDD3V3_7") (pintype "bidirectional"))
      (node (ref "XA3") (pin "6") (pinfunction "VDD3V3_6") (pintype "bidirectional"))
      (node (ref "XA3") (pin "7") (pinfunction "VDD3V3_7") (pintype "bidirectional"))
      (node (ref "XA4") (pin "P29") (pinfunction "P29-VDD_P29") (pintype "bidirectional"))
    )
    (net (code "3") (name "9DOF_BL_IND") (class "Default")
      (node (ref "U6") (pin "10") (pinfunction "BL_IND_10") (pintype "output"))
      (node (ref "XA4") (pin "P47") (pinfunction "P47-AP4_GP14/TT_9DOF_BL_IND_P47") (pintype "bidirectional"))
    )
    (net (code "4") (name "9DOF_INT") (class "Default")
      (node (ref "U6") (pin "14") (pinfunction "INT_14") (pintype "output"))
      (node (ref "XA4") (pin "P48") (pinfunction "P48-AP4_GP17/TT_9DOF_INT_P48") (pintype "bidirectional"))
    )
    (net (code "5") (name "9DOF_SCL-COM1") (class "Default")
      (node (ref "RX6") (pin "2") (pinfunction "2_2") (pintype "passive"))
      (node (ref "U6") (pin "19") (pinfunction "COM1_19") (pintype "bidirectional"))
      (node (ref "XA4") (pin "P30") (pinfunction "P30-AP4_GP08/TT_9DOF_SCL_COM1_P30") (pintype "bidirectional"))
    )
    (net (code "6") (name "9DOF_SDA-COM0") (class "Default")
      (node (ref "RX5") (pin "2") (pinfunction "2_2") (pintype "passive"))
      (node (ref "U6") (pin "20") (pinfunction "COM0_20") (pintype "bidirectional"))
      (node (ref "XA4") (pin "P31") (pinfunction "P31-AP4_GP09/TT_9DOF_SDA_COM0_P31") (pintype "bidirectional"))
    )
    (net (code "7") (name "9DOF_SWCLK") (class "Default")
      (node (ref "J1") (pin "4") (pinfunction "SWDCLK_4") (pintype "bidirectional"))
      (node (ref "U6") (pin "8") (pinfunction "SWCLK_8") (pintype "input"))
    )
    (net (code "8") (name "9DOF_SWDIO") (class "Default")
      (node (ref "J1") (pin "2") (pinfunction "SWDIO_2") (pintype "bidirectional"))
      (node (ref "U6") (pin "7") (pinfunction "SWDIO_7") (pintype "bidirectional"))
    )
    (net (code "9") (name "9DOF_~{BOOT_LOAD_PIN}") (class "Default")
      (node (ref "R20") (pin "1") (pinfunction "1_1") (pintype "passive"))
      (node (ref "U6") (pin "4") (pinfunction "~{BOOT_LOAD_PIN}_4") (pintype "input"))
      (node (ref "XA4") (pin "P46") (pinfunction "P46-AP4_GP13/TT_9DOF_~{BL_PIN}_P46") (pintype "bidirectional"))
    )
    (net (code "10") (name "9DOF_~{RESET}") (class "Default")
      (node (ref "J1") (pin "3") (pinfunction "~{RESET}_3") (pintype "bidirectional"))
      (node (ref "RX8") (pin "1") (pinfunction "1_1") (pintype "passive"))
      (node (ref "U6") (pin "11") (pinfunction "~{RESET}_11") (pintype "bidirectional"))
      (node (ref "XA4") (pin "P45") (pinfunction "P45-AP4_GP65/TT_9DOF_~{RESET}_P45") (pintype "bidirectional"))
    )
    (net (code "11") (name "AGND") (class "Default")
      (node (ref "C1") (pin "2") (pinfunction "2_2") (pintype "bidirectional"))
      (node (ref "C2") (pin "2") (pinfunction "2_2") (pintype "bidirectional"))
      (node (ref "XA4") (pin "P14") (pinfunction "P14-AGND_P14") (pintype "bidirectional"))
    )
    (net (code "12") (name "AP4_LED1_GREEN") (class "Default")
      (node (ref "R2") (pin "2") (pinfunction "2_2") (pintype "passive"))
      (node (ref "XA4") (pin "P40") (pinfunction "P40-AP4_GP51/LED1_GREEN_P40") (pintype "bidirectional"))
    )
    (net (code "13") (name "AP4_LED1_RED") (class "Default")
      (node (ref "R5") (pin "2") (pinfunction "2_2") (pintype "passive"))
      (node (ref "XA4") (pin "P41") (pinfunction "P41-AP4_GP53/LED1_RED_P41") (pintype "bidirectional"))
    )
    (net (code "14") (name "BATIN") (class "Default")
      (node (ref "C27") (pin "1") (pinfunction "1_1") (pintype "bidirectional"))
      (node (ref "R30") (pin "2") (pinfunction "2_2") (pintype "passive"))
      (node (ref "R31") (pin "1") (pinfunction "1_1") (pintype "passive"))
      (node (ref "XA4") (pin "P4") (pinfunction "P4-AP4_GP18/TT_BATIN_P4") (pintype "bidirectional"))
    )
    (net (code "15") (name "BATT_THERM") (class "Default")
      (node (ref "J4") (pin "2") (pinfunction "2_2") (pintype "bidirectional"))
      (node (ref "J4") (pin "2SUPP") (pinfunction "2_2SUPP") (pintype "bidirectional"))
      (node (ref "JP2") (pin "3") (pinfunction "3_3") (pintype "passive"))
    )
    (net (code "16") (name "BATT_TS") (class "Default")
      (node (ref "JP2") (pin "2") (pinfunction "2_2") (pintype "passive"))
      (node (ref "U3") (pin "9") (pinfunction "TS_9") (pintype "bidirectional"))
    )
    (net (code "17") (name "BUZZER_GATE") (class "Default")
      (node (ref "Q2") (pin "G") (pinfunction "G_G") (pintype "passive"))
      (node (ref "R25") (pin "1") (pinfunction "1_1") (pintype "passive"))
      (node (ref "XA4") (pin "P33") (pinfunction "P33-AP4_GP55/TT_BUZZER_GATE_P33") (pintype "bidirectional"))
    )
    (net (code "18") (name "DWM1_IRQ") (class "Default")
      (node (ref "R24") (pin "2") (pinfunction "2_2") (pintype "passive"))
      (node (ref "XA1") (pin "22") (pinfunction "IRQ/GP8_22") (pintype "bidirectional"))
      (node (ref "XA4") (pin "P35") (pinfunction "P35-AP4_GP27/TT_DW_IRQ_P35") (pintype "bidirectional"))
    )
    (net (code "19") (name "DWM1_WAKEUP") (class "Default")
      (node (ref "XA1") (pin "2") (pinfunction "WAKEUP_2") (pintype "input"))
      (node (ref "XA4") (pin "P34") (pinfunction "P34-AP4_GP26/TT_DW_WAKEUP_P34") (pintype "bidirectional"))
    )
    (net (code "20") (name "DWM2_IRQ") (class "Default")
      (node (ref "R1") (pin "2") (pinfunction "2_2") (pintype "passive"))
      (node (ref "XA2") (pin "22") (pinfunction "IRQ/GP8_22") (pintype "bidirectional"))
      (node (ref "XA4") (pin "P39") (pinfunction "P39-AP4_GP72_P39") (pintype "bidirectional"))
    )
    (net (code "21") (name "DWM2_WAKEUP") (class "Default")
      (node (ref "XA2") (pin "2") (pinfunction "WAKEUP_2") (pintype "input"))
      (node (ref "XA4") (pin "P25") (pinfunction "P25-AP4_GP63_P25") (pintype "bidirectional"))
    )
    (net (code "22") (name "DWM3_IRQ") (class "Default")
      (node (ref "R10") (pin "2") (pinfunction "2_2") (pintype "passive"))
      (node (ref "XA3") (pin "22") (pinfunction "IRQ/GP8_22") (pintype "bidirectional"))
      (node (ref "XA4") (pin "P22") (pinfunction "P22-AP4_GP76_P22") (pintype "bidirectional"))
    )
    (net (code "23") (name "DWM3_WAKEUP") (class "Default")
      (node (ref "XA3") (pin "2") (pinfunction "WAKEUP_2") (pintype "input"))
      (node (ref "XA4") (pin "P32") (pinfunction "P32-AP4_GP88_P32") (pintype "bidirectional"))
    )
    (net (code "24") (name "DW_SPI_CIPO") (class "Default")
      (node (ref "XA1") (pin "19") (pinfunction "SPI_MISO_19") (pintype "output"))
      (node (ref "XA2") (pin "19") (pinfunction "SPI_MISO_19") (pintype "output"))
      (node (ref "XA3") (pin "19") (pinfunction "SPI_MISO_19") (pintype "output"))
      (node (ref "XA4") (pin "P10") (pinfunction "P10-AP4_GP33/TT_DW_SPI_IO1_P10") (pintype "bidirectional"))
    )
    (net (code "25") (name "DW_SPI_CLK") (class "Default")
      (node (ref "XA1") (pin "20") (pinfunction "SPI_CLK_20") (pintype "input"))
      (node (ref "XA2") (pin "20") (pinfunction "SPI_CLK_20") (pintype "input"))
      (node (ref "XA3") (pin "20") (pinfunction "SPI_CLK_20") (pintype "input"))
      (node (ref "XA4") (pin "P12") (pinfunction "P12-AP4_GP31/TT_DW_SPI_CLK_P12") (pintype "bidirectional"))
    )
    (net (code "26") (name "DW_SPI_COPI") (class "Default")
      (node (ref "XA1") (pin "18") (pinfunction "SPI_MOSI_18") (pintype "input"))
      (node (ref "XA2") (pin "18") (pinfunction "SPI_MOSI_18") (pintype "input"))
      (node (ref "XA3") (pin "18") (pinfunction "SPI_MOSI_18") (pintype "input"))
      (node (ref "XA4") (pin "P11") (pinfunction "P11-AP4_GP32/TT_DW_SPI_IO0_P11") (pintype "bidirectional"))
    )
    (net (code "27") (name "FLASH_CLK") (class "Default")
      (node (ref "U5") (pin "6") (pinfunction "CLK_6") (pintype "input"))
      (node (ref "XA4") (pin "P7") (pinfunction "P7-AP4_GP47/TT_FLASH_SCK_P7") (pintype "bidirectional"))
    )
    (net (code "28") (name "FLASH_PDI-IO0") (class "Default")
      (node (ref "U5") (pin "5") (pinfunction "DI_5") (pintype "bidirectional"))
      (node (ref "XA4") (pin "P6") (pinfunction "P6-AP4_GP48/TT_FLASH_MOSI_P6") (pintype "bidirectional"))
    )
    (net (code "29") (name "FLASH_PDO-IO1") (class "Default")
      (node (ref "U5") (pin "2") (pinfunction "DO_2") (pintype "bidirectional"))
      (node (ref "XA4") (pin "P5") (pinfunction "P5-AP4_GP49/TT_FLASH_MISO_P5") (pintype "bidirectional"))
    )
    (net (code "30") (name "FLASH_~{CS}") (class "Default")
      (node (ref "R21") (pin "1") (pinfunction "1_1") (pintype "passive"))
      (node (ref "U5") (pin "1") (pinfunction "~{CS}_1") (pintype "input"))
      (node (ref "XA4") (pin "P42") (pinfunction "P42-AP4_GP69/TT_FLASH_~{CS}_P42") (pintype "bidirectional"))
    )
    (net (code "31") (name "FLASH_~{HOLD}-IO3") (class "Default")
      (node (ref "U5") (pin "7") (pinfunction "~{HOLD}_7") (pintype "bidirectional"))
      (node (ref "XA4") (pin "P24") (pinfunction "P24-AP4_GP06/TT_FLASH_~{HOLD}_P24") (pintype "bidirectional"))
    )
    (net (code "32") (name "FLASH_~{WP}-IO2") (class "Default")
      (node (ref "U5") (pin "3") (pinfunction "~{WP}_3") (pintype "bidirectional"))
      (node (ref "XA4") (pin "P23") (pinfunction "P23-AP4_GP30/TT_FLASH_~{WP}_P23") (pintype "bidirectional"))
    )
    (net (code "33") (name "GND") (class "Default")
      (node (ref "C27") (pin "2") (pinfunction "2_2") (pintype "bidirectional"))
      (node (ref "C28") (pin "2") (pinfunction "2_2") (pintype "bidirectional"))
      (node (ref "C29") (pin "2") (pinfunction "2_2") (pintype "bidirectional"))
      (node (ref "C30") (pin "2") (pinfunction "2_2") (pintype "bidirectional"))
      (node (ref "C31") (pin "2") (pinfunction "2_2") (pintype "bidirectional"))
      (node (ref "C32") (pin "2") (pinfunction "2_2") (pintype "bidirectional"))
      (node (ref "C35") (pin "2") (pinfunction "2_2") (pintype "bidirectional"))
      (node (ref "C41") (pin "2") (pinfunction "2_2") (pintype "bidirectional"))
      (node (ref "C42") (pin "2") (pinfunction "2_2") (pintype "bidirectional"))
      (node (ref "C43") (pin "2") (pinfunction "2_2") (pintype "bidirectional"))
      (node (ref "C44") (pin "2") (pinfunction "2_2") (pintype "bidirectional"))
      (node (ref "C45") (pin "1") (pinfunction "1_1") (pintype "bidirectional"))
      (node (ref "C46") (pin "2") (pinfunction "2_2") (pintype "bidirectional"))
      (node (ref "C47") (pin "1") (pinfunction "1_1") (pintype "bidirectional"))
      (node (ref "C48") (pin "2") (pinfunction "2_2") (pintype "bidirectional"))
      (node (ref "C5") (pin "P$1") (pinfunction "1_P$1") (pintype "bidirectional"))
      (node (ref "C53") (pin "2") (pinfunction "2_2") (pintype "bidirectional"))
      (node (ref "C56") (pin "2") (pinfunction "2_2") (pintype "bidirectional"))
      (node (ref "C57") (pin "2") (pinfunction "2_2") (pintype "bidirectional"))
      (node (ref "C6") (pin "P$1") (pinfunction "1_P$1") (pintype "bidirectional"))
      (node (ref "J1") (pin "5") (pinfunction "GND_5") (pintype "bidirectional"))
      (node (ref "J4") (pin "1") (pinfunction "1_1") (pintype "bidirectional"))
      (node (ref "J4") (pin "1SUPP") (pinfunction "1_1SUPP") (pintype "bidirectional"))
      (node (ref "JP6") (pin "1") (pinfunction "1_1") (pintype "passive"))
      (node (ref "JP9") (pin "2") (pinfunction "2_2") (pintype "passive"))
      (node (ref "Q2") (pin "S") (pinfunction "S_S") (pintype "passive"))
      (node (ref "R1") (pin "1") (pinfunction "1_1") (pintype "passive"))
      (node (ref "R10") (pin "1") (pinfunction "1_1") (pintype "passive"))
      (node (ref "R14") (pin "1") (pinfunction "1_1") (pintype "passive"))
      (node (ref "R15") (pin "1") (pinfunction "1_1") (pintype "passive"))
      (node (ref "R24") (pin "1") (pinfunction "1_1") (pintype "passive"))
      (node (ref "R25") (pin "2") (pinfunction "2_2") (pintype "passive"))
      (node (ref "R26") (pin "1") (pinfunction "1_1") (pintype "passive"))
      (node (ref "R27") (pin "1") (pinfunction "1_1") (pintype "passive"))
      (node (ref "R30") (pin "1") (pinfunction "1_1") (pintype "passive"))
      (node (ref "R6") (pin "2") (pinfunction "2_2") (pintype "passive"))
      (node (ref "RX7") (pin "1") (pinfunction "1_1") (pintype "passive"))
      (node (ref "U3") (pin "3") (pinfunction "VSS_3") (pintype "bidirectional"))
      (node (ref "U3") (pin "7") (pinfunction "ISET2_7") (pintype "bidirectional"))
      (node (ref "U3") (pin "PAD") (pinfunction "VSS_PAD") (pintype "bidirectional"))
      (node (ref "U4") (pin "1") (pinfunction "PGND_1") (pintype "bidirectional"))
      (node (ref "U4") (pin "10") (pinfunction "EN1_10") (pintype "bidirectional"))
      (node (ref "U4") (pin "11") (pinfunction "EN2_11") (pintype "bidirectional"))
      (node (ref "U4") (pin "20") (pinfunction "PGND_20") (pintype "bidirectional"))
      (node (ref "U4") (pin "9") (pinfunction "AD_9") (pintype "bidirectional"))
      (node (ref "U4") (pin "PAD") (pinfunction "PGND_PAD") (pintype "bidirectional"))
      (node (ref "U5") (pin "4") (pinfunction "GND_4") (pintype "bidirectional"))
      (node (ref "U6") (pin "18") (pinfunction "COM2_18") (pintype "bidirectional"))
      (node (ref "U6") (pin "2") (pinfunction "GND_2") (pintype "bidirectional"))
      (node (ref "U6") (pin "25") (pinfunction "GNDIO_25") (pintype "bidirectional"))
      (node (ref "U6") (pin "5") (pinfunction "PS1_5") (pintype "input"))
      (node (ref "U6") (pin "6") (pinfunction "PS0_6") (pintype "input"))
      (node (ref "VR1") (pin "13") (pinfunction "GND2_13") (pintype "bidirectional"))
      (node (ref "VR1") (pin "3") (pinfunction "GND2_3") (pintype "bidirectional"))
      (node (ref "VR1") (pin "9") (pinfunction "GND1_9") (pintype "bidirectional"))
      (node (ref "XA1") (pin "16") (pinfunction "VSS_16") (pintype "bidirectional"))
      (node (ref "XA1") (pin "21") (pinfunction "VSS_21") (pintype "bidirectional"))
      (node (ref "XA1") (pin "23") (pinfunction "VSS_23") (pintype "bidirectional"))
      (node (ref "XA1") (pin "24") (pinfunction "VSS_24") (pintype "bidirectional"))
      (node (ref "XA1") (pin "8") (pinfunction "VSS_8") (pintype "bidirectional"))
      (node (ref "XA2") (pin "16") (pinfunction "VSS_16") (pintype "bidirectional"))
      (node (ref "XA2") (pin "21") (pinfunction "VSS_21") (pintype "bidirectional"))
      (node (ref "XA2") (pin "23") (pinfunction "VSS_23") (pintype "bidirectional"))
      (node (ref "XA2") (pin "24") (pinfunction "VSS_24") (pintype "bidirectional"))
      (node (ref "XA2") (pin "8") (pinfunction "VSS_8") (pintype "bidirectional"))
      (node (ref "XA3") (pin "16") (pinfunction "VSS_16") (pintype "bidirectional"))
      (node (ref "XA3") (pin "21") (pinfunction "VSS_21") (pintype "bidirectional"))
      (node (ref "XA3") (pin "23") (pinfunction "VSS_23") (pintype "bidirectional"))
      (node (ref "XA3") (pin "24") (pinfunction "VSS_24") (pintype "bidirectional"))
      (node (ref "XA3") (pin "8") (pinfunction "VSS_8") (pintype "bidirectional"))
      (node (ref "XA4") (pin "P13") (pinfunction "P13-GND_P13") (pintype "bidirectional"))
      (node (ref "XA4") (pin "P37") (pinfunction "P37-GND_P37") (pintype "bidirectional"))
      (node (ref "XR19") (pin "1") (pinfunction "1_1") (pintype "passive"))
    )
    (net (code "34") (name "GP82{slash}SWTRACE2") (class "Default")
      (node (ref "RZ2") (pin "2") (pinfunction "2_2") (pintype "passive"))
      (node (ref "XA4") (pin "P18") (pinfunction "P18-AP4_GP82/SWTRACE2_P18") (pintype "bidirectional"))
    )
    (net (code "35") (name "GP83{slash}SWTRACE3") (class "Default")
      (node (ref "RZ3") (pin "2") (pinfunction "2_2") (pintype "passive"))
      (node (ref "XA4") (pin "P19") (pinfunction "P19-AP4_GP82/SWTRACE3_P19") (pintype "bidirectional"))
    )
    (net (code "36") (name "Net-(A4-ANTENNA)") (class "Default")
      (node (ref "A4") (pin "S1") (pinfunction "ANTENNA_S1") (pintype "bidirectional"))
      (node (ref "C1") (pin "1") (pinfunction "1_1") (pintype "bidirectional"))
      (node (ref "L3") (pin "1") (pinfunction "1_1") (pintype "bidirectional"))
    )
    (net (code "37") (name "Net-(C5-2)") (class "Default")
      (node (ref "C5") (pin "P$2") (pinfunction "2_P$2") (pintype "bidirectional"))
      (node (ref "U6") (pin "27") (pinfunction "XIN32_27") (pintype "bidirectional"))
      (node (ref "X2") (pin "2") (pinfunction "2_2") (pintype "bidirectional"))
    )
    (net (code "38") (name "Net-(C6-2)") (class "Default")
      (node (ref "C6") (pin "P$2") (pinfunction "2_P$2") (pintype "bidirectional"))
      (node (ref "U6") (pin "26") (pinfunction "XOUT32_26") (pintype "bidirectional"))
      (node (ref "X2") (pin "1") (pinfunction "1_1") (pintype "bidirectional"))
    )
    (net (code "39") (name "Net-(C7-2)") (class "Default")
      (node (ref "C7") (pin "P$2") (pinfunction "2_P$2") (pintype "bidirectional"))
      (node (ref "R26") (pin "2") (pinfunction "2_2") (pintype "passive"))
      (node (ref "R28") (pin "1") (pinfunction "1_1") (pintype "passive"))
      (node (ref "VR1") (pin "10") (pinfunction "FB2_10") (pintype "bidirectional"))
    )
    (net (code "40") (name "Net-(C8-1)") (class "Default")
      (node (ref "C8") (pin "P$1") (pinfunction "1_P$1") (pintype "bidirectional"))
      (node (ref "R27") (pin "2") (pinfunction "2_2") (pintype "passive"))
      (node (ref "R29") (pin "2") (pinfunction "2_2") (pintype "passive"))
      (node (ref "VR1") (pin "4") (pinfunction "FB1_4") (pintype "bidirectional"))
    )
    (net (code "41") (name "Net-(D1-PadA1)") (class "Default")
      (node (ref "D1") (pin "A1") (pinfunction "A1_A1") (pintype "bidirectional"))
      (node (ref "D1") (pin "A2") (pinfunction "A2_A2") (pintype "bidirectional"))
      (node (ref "RZ1") (pin "1") (pinfunction "1_1") (pintype "passive"))
    )
    (net (code "42") (name "Net-(D1-PadC1)") (class "Default")
      (node (ref "D1") (pin "C1") (pinfunction "C1_C1") (pintype "bidirectional"))
      (node (ref "R5") (pin "1") (pinfunction "1_1") (pintype "passive"))
    )
    (net (code "43") (name "Net-(D1-PadC2)") (class "Default")
      (node (ref "D1") (pin "C2") (pinfunction "C2_C2") (pintype "bidirectional"))
      (node (ref "R2") (pin "1") (pinfunction "1_1") (pintype "passive"))
    )
    (net (code "44") (name "Net-(JP2-Pad1)") (class "Default")
      (node (ref "JP2") (pin "1") (pinfunction "1_1") (pintype "passive"))
      (node (ref "XR19") (pin "2") (pinfunction "2_2") (pintype "passive"))
    )
    (net (code "45") (name "Net-(L1-1)") (class "Default")
      (node (ref "L1") (pin "P$1") (pinfunction "1_P$1") (pintype "bidirectional"))
      (node (ref "VR1") (pin "2") (pinfunction "LX2_2") (pintype "bidirectional"))
    )
    (net (code "46") (name "Net-(L2-2)") (class "Default")
      (node (ref "L2") (pin "P$2") (pinfunction "2_P$2") (pintype "bidirectional"))
      (node (ref "VR1") (pin "8") (pinfunction "LX1_8") (pintype "bidirectional"))
    )
    (net (code "47") (name "Net-(L4-1)") (class "Default")
      (node (ref "C17") (pin "2") (pinfunction "2_2") (pintype "bidirectional"))
      (node (ref "C18") (pin "2") (pinfunction "2_2") (pintype "bidirectional"))
      (node (ref "C19") (pin "2") (pinfunction "2_2") (pintype "bidirectional"))
      (node (ref "L4") (pin "P$1") (pinfunction "1_P$1") (pintype "bidirectional"))
    )
    (net (code "48") (name "Net-(L4-2)") (class "Default")
      (node (ref "C10") (pin "2") (pinfunction "2_2") (pintype "bidirectional"))
      (node (ref "C16") (pin "2") (pinfunction "2_2") (pintype "bidirectional"))
      (node (ref "C21") (pin "2") (pinfunction "2_2") (pintype "bidirectional"))
      (node (ref "C39") (pin "2") (pinfunction "2_2") (pintype "bidirectional"))
      (node (ref "C9") (pin "2") (pinfunction "2_2") (pintype "bidirectional"))
      (node (ref "L4") (pin "P$2") (pinfunction "2_P$2") (pintype "bidirectional"))
      (node (ref "U4") (pin "19") (pinfunction "AC2_19") (pintype "bidirectional"))
    )
    (net (code "49") (name "Net-(LS1-N)") (class "Default")
      (node (ref "D4") (pin "ANODE") (pinfunction "ANODE_ANODE") (pintype "bidirectional"))
      (node (ref "LS1") (pin "-") (pinfunction "N_-") (pintype "passive"))
      (node (ref "Q2") (pin "D") (pinfunction "D_D") (pintype "passive"))
    )
    (net (code "50") (name "Net-(LS1-P)") (class "Default")
      (node (ref "C44") (pin "1") (pinfunction "1_1") (pintype "bidirectional"))
      (node (ref "D4") (pin "CATHODE") (pinfunction "CATHODE_CATHODE") (pintype "bidirectional"))
      (node (ref "JP8") (pin "2") (pinfunction "2_2") (pintype "passive"))
      (node (ref "LS1") (pin "+") (pinfunction "P_+") (pintype "passive"))
    )
    (net (code "51") (name "Net-(R6-Pad1)") (class "Default")
      (node (ref "R6") (pin "1") (pinfunction "1_1") (pintype "passive"))
      (node (ref "R7") (pin "2") (pinfunction "2_2") (pintype "passive"))
    )
    (net (code "52") (name "Net-(R8-Pad2)") (class "Default")
      (node (ref "R8") (pin "2") (pinfunction "2_2") (pintype "passive"))
      (node (ref "R9") (pin "1") (pinfunction "1_1") (pintype "passive"))
    )
    (net (code "53") (name "Net-(R13-Pad1)") (class "Default")
      (node (ref "R13") (pin "1") (pinfunction "1_1") (pintype "passive"))
      (node (ref "R14") (pin "2") (pinfunction "2_2") (pintype "passive"))
    )
    (net (code "54") (name "Net-(R13-Pad2)") (class "Default")
      (node (ref "R13") (pin "2") (pinfunction "2_2") (pintype "passive"))
      (node (ref "RT1") (pin "1") (pinfunction "1_1") (pintype "passive"))
    )
    (net (code "55") (name "Net-(R18-Pad2)") (class "Default")
      (node (ref "R18") (pin "2") (pinfunction "2_2") (pintype "passive"))
      (node (ref "R23") (pin "1") (pinfunction "1_1") (pintype "passive"))
    )
    (net (code "56") (name "Net-(U3-ISET)") (class "Default")
      (node (ref "R15") (pin "2") (pinfunction "2_2") (pintype "passive"))
      (node (ref "U3") (pin "2") (pinfunction "ISET_2") (pintype "bidirectional"))
    )
    (net (code "57") (name "Net-(U3-PRETERM)") (class "Default")
      (node (ref "RX7") (pin "2") (pinfunction "2_2") (pintype "passive"))
      (node (ref "U3") (pin "4") (pinfunction "PRETERM_4") (pintype "bidirectional"))
    )
    (net (code "58") (name "Net-(U4-AC1)") (class "Default")
      (node (ref "C10") (pin "1") (pinfunction "1_1") (pintype "bidirectional"))
      (node (ref "C15") (pin "2") (pinfunction "2_2") (pintype "bidirectional"))
      (node (ref "C17") (pin "1") (pinfunction "1_1") (pintype "bidirectional"))
      (node (ref "C18") (pin "1") (pinfunction "1_1") (pintype "bidirectional"))
      (node (ref "C19") (pin "1") (pinfunction "1_1") (pintype "bidirectional"))
      (node (ref "C20") (pin "2") (pinfunction "2_2") (pintype "bidirectional"))
      (node (ref "C38") (pin "2") (pinfunction "2_2") (pintype "bidirectional"))
      (node (ref "C9") (pin "1") (pinfunction "1_1") (pintype "bidirectional"))
      (node (ref "U4") (pin "2") (pinfunction "AC1_2") (pintype "bidirectional"))
    )
    (net (code "59") (name "Net-(U4-BOOT1)") (class "Default")
      (node (ref "C15") (pin "1") (pinfunction "1_1") (pintype "bidirectional"))
      (node (ref "U4") (pin "3") (pinfunction "BOOT1_3") (pintype "bidirectional"))
    )
    (net (code "60") (name "Net-(U4-BOOT2)") (class "Default")
      (node (ref "C16") (pin "1") (pinfunction "1_1") (pintype "bidirectional"))
      (node (ref "U4") (pin "17") (pinfunction "BOOT2_17") (pintype "bidirectional"))
    )
    (net (code "61") (name "Net-(U4-CLAMP1)") (class "Default")
      (node (ref "C38") (pin "1") (pinfunction "1_1") (pintype "bidirectional"))
      (node (ref "U4") (pin "5") (pinfunction "CLAMP1_5") (pintype "bidirectional"))
    )
    (net (code "62") (name "Net-(U4-CLAMP2)") (class "Default")
      (node (ref "C39") (pin "1") (pinfunction "1_1") (pintype "bidirectional"))
      (node (ref "U4") (pin "16") (pinfunction "CLAMP2_16") (pintype "bidirectional"))
    )
    (net (code "63") (name "Net-(U4-COMM1)") (class "Default")
      (node (ref "C20") (pin "1") (pinfunction "1_1") (pintype "bidirectional"))
      (node (ref "U4") (pin "6") (pinfunction "COMM1_6") (pintype "bidirectional"))
    )
    (net (code "64") (name "Net-(U4-COMM2)") (class "Default")
      (node (ref "C21") (pin "1") (pinfunction "1_1") (pintype "bidirectional"))
      (node (ref "U4") (pin "15") (pinfunction "COMM2_15") (pintype "bidirectional"))
    )
    (net (code "65") (name "Net-(U4-FOD)") (class "Default")
      (node (ref "R23") (pin "2") (pinfunction "2_2") (pintype "passive"))
      (node (ref "R7") (pin "1") (pinfunction "1_1") (pintype "passive"))
      (node (ref "R9") (pin "2") (pinfunction "2_2") (pintype "passive"))
      (node (ref "U4") (pin "14") (pinfunction "FOD_14") (pintype "bidirectional"))
    )
    (net (code "66") (name "Net-(U4-ILIM)") (class "Default")
      (node (ref "R8") (pin "1") (pinfunction "1_1") (pintype "passive"))
      (node (ref "U4") (pin "12") (pinfunction "ILIM_12") (pintype "bidirectional"))
    )
    (net (code "67") (name "Net-(U4-RECT)") (class "Default")
      (node (ref "C28") (pin "1") (pinfunction "1_1") (pintype "bidirectional"))
      (node (ref "C56") (pin "1") (pinfunction "1_1") (pintype "bidirectional"))
      (node (ref "C57") (pin "1") (pinfunction "1_1") (pintype "bidirectional"))
      (node (ref "R18") (pin "1") (pinfunction "1_1") (pintype "passive"))
      (node (ref "U4") (pin "18") (pinfunction "RECT_18") (pintype "bidirectional"))
    )
    (net (code "68") (name "Net-(U6-CAP)") (class "Default")
      (node (ref "C43") (pin "1") (pinfunction "1_1") (pintype "bidirectional"))
      (node (ref "U6") (pin "9") (pinfunction "CAP_9") (pintype "bidirectional"))
    )
    (net (code "69") (name "Net-(U6-COM3)") (class "Default")
      (node (ref "JP6") (pin "2") (pinfunction "2_2") (pintype "passive"))
      (node (ref "U6") (pin "17") (pinfunction "COM3_17") (pintype "bidirectional"))
    )
    (net (code "70") (name "Net-(XA4-P15-BLE_RFOUT)") (class "Default")
      (node (ref "C2") (pin "1") (pinfunction "1_1") (pintype "bidirectional"))
      (node (ref "L3") (pin "2") (pinfunction "2_2") (pintype "bidirectional"))
      (node (ref "XA4") (pin "P15") (pinfunction "P15-BLE_RFOUT_P15") (pintype "bidirectional"))
    )
    (net (code "71") (name "QI_TS_CTRL") (class "Default")
      (node (ref "C30") (pin "1") (pinfunction "1_1") (pintype "bidirectional"))
      (node (ref "RT1") (pin "2") (pinfunction "2_2") (pintype "passive"))
      (node (ref "U4") (pin "13") (pinfunction "TS/CTRL_13") (pintype "bidirectional"))
      (node (ref "XA4") (pin "P44") (pinfunction "P44-AP4_GP66/TT_QI_TS_CTRL_P44") (pintype "bidirectional"))
    )
    (net (code "72") (name "VBAT") (class "Default")
      (node (ref "C42") (pin "1") (pinfunction "1_1") (pintype "bidirectional"))
      (node (ref "J4") (pin "3") (pinfunction "3_3") (pintype "bidirectional"))
      (node (ref "J4") (pin "3SUPP") (pinfunction "3_3SUPP") (pintype "bidirectional"))
      (node (ref "JP9") (pin "1") (pinfunction "1_1") (pintype "passive"))
      (node (ref "S1") (pin "2") (pinfunction "2_2") (pintype "passive"))
      (node (ref "U3") (pin "10") (pinfunction "OUT_10") (pintype "bidirectional"))
    )
    (net (code "73") (name "VBAT_SWITCHED") (class "Default")
      (node (ref "C45") (pin "2") (pinfunction "2_2") (pintype "bidirectional"))
      (node (ref "C48") (pin "1") (pinfunction "1_1") (pintype "bidirectional"))
      (node (ref "JP8") (pin "1") (pinfunction "1_1") (pintype "passive"))
      (node (ref "R31") (pin "2") (pinfunction "2_2") (pintype "passive"))
      (node (ref "S1") (pin "3") (pinfunction "3_3") (pintype "passive"))
      (node (ref "VR1") (pin "1") (pinfunction "VIN2_1") (pintype "bidirectional"))
      (node (ref "VR1") (pin "12") (pinfunction "EN2_12") (pintype "bidirectional"))
      (node (ref "VR1") (pin "6") (pinfunction "EN1_6") (pintype "bidirectional"))
      (node (ref "VR1") (pin "7") (pinfunction "VIN1_7") (pintype "bidirectional"))
    )
    (net (code "74") (name "VQI") (class "Default")
      (node (ref "C29") (pin "1") (pinfunction "1_1") (pintype "bidirectional"))
      (node (ref "C41") (pin "1") (pinfunction "1_1") (pintype "bidirectional"))
      (node (ref "C53") (pin "1") (pinfunction "1_1") (pintype "bidirectional"))
      (node (ref "U3") (pin "1") (pinfunction "IN_1") (pintype "bidirectional"))
      (node (ref "U4") (pin "4") (pinfunction "OUT_4") (pintype "bidirectional"))
    )
    (net (code "75") (name "unconnected-(J1-SWO-Pad6)") (class "Default")
      (node (ref "J1") (pin "6") (pinfunction "SWO_6") (pintype "bidirectional"))
    )
    (net (code "76") (name "unconnected-(S1-Pad1)") (class "Default")
      (node (ref "S1") (pin "1") (pinfunction "1_1") (pintype "passive"))
    )
    (net (code "77") (name "unconnected-(U4-~{AD-EN}-Pad8)") (class "Default")
      (node (ref "U4") (pin "8") (pinfunction "~{AD-EN}_8") (pintype "bidirectional"))
    )
    (net (code "78") (name "unconnected-(VR1-NC1-Pad5)") (class "Default")
      (node (ref "VR1") (pin "5") (pinfunction "NC1_5") (pintype "bidirectional"))
    )
    (net (code "79") (name "unconnected-(VR1-NC2-Pad11)") (class "Default")
      (node (ref "VR1") (pin "11") (pinfunction "NC2_11") (pintype "bidirectional"))
    )
    (net (code "80") (name "unconnected-(XA1-EXTON-Pad1)") (class "Default")
      (node (ref "XA1") (pin "1") (pinfunction "EXTON_1") (pintype "output"))
    )
    (net (code "81") (name "unconnected-(XA1-GP4-Pad11)") (class "Default")
      (node (ref "XA1") (pin "11") (pinfunction "GP4_11") (pintype "bidirectional"))
    )
    (net (code "82") (name "unconnected-(XA1-RXLED{slash}GP2-Pad13)") (class "Default")
      (node (ref "XA1") (pin "13") (pinfunction "RXLED/GP2_13") (pintype "bidirectional"))
    )
    (net (code "83") (name "unconnected-(XA1-RXOKLED{slash}GP0-Pad15)") (class "Default")
      (node (ref "XA1") (pin "15") (pinfunction "RXOKLED/GP0_15") (pintype "bidirectional"))
    )
    (net (code "84") (name "unconnected-(XA1-SFDLED{slash}GP1-Pad14)") (class "Default")
      (node (ref "XA1") (pin "14") (pinfunction "SFDLED/GP1_14") (pintype "bidirectional"))
    )
    (net (code "85") (name "unconnected-(XA1-SPI_PHA{slash}GP6-Pad9)") (class "Default")
      (node (ref "XA1") (pin "9") (pinfunction "SPI_PHA/GP6_9") (pintype "bidirectional"))
    )
    (net (code "86") (name "unconnected-(XA1-SPI_POL{slash}GP5-Pad10)") (class "Default")
      (node (ref "XA1") (pin "10") (pinfunction "SPI_POL/GP5_10") (pintype "bidirectional"))
    )
    (net (code "87") (name "unconnected-(XA1-SYNC{slash}GP7-Pad4)") (class "Default")
      (node (ref "XA1") (pin "4") (pinfunction "SYNC/GP7_4") (pintype "bidirectional"))
    )
    (net (code "88") (name "unconnected-(XA1-TXLED{slash}GP3-Pad12)") (class "Default")
      (node (ref "XA1") (pin "12") (pinfunction "TXLED/GP3_12") (pintype "bidirectional"))
    )
    (net (code "89") (name "unconnected-(XA2-EXTON-Pad1)") (class "Default")
      (node (ref "XA2") (pin "1") (pinfunction "EXTON_1") (pintype "output"))
    )
    (net (code "90") (name "unconnected-(XA2-GP4-Pad11)") (class "Default")
      (node (ref "XA2") (pin "11") (pinfunction "GP4_11") (pintype "bidirectional"))
    )
    (net (code "91") (name "unconnected-(XA2-RXLED{slash}GP2-Pad13)") (class "Default")
      (node (ref "XA2") (pin "13") (pinfunction "RXLED/GP2_13") (pintype "bidirectional"))
    )
    (net (code "92") (name "unconnected-(XA2-RXOKLED{slash}GP0-Pad15)") (class "Default")
      (node (ref "XA2") (pin "15") (pinfunction "RXOKLED/GP0_15") (pintype "bidirectional"))
    )
    (net (code "93") (name "unconnected-(XA2-SFDLED{slash}GP1-Pad14)") (class "Default")
      (node (ref "XA2") (pin "14") (pinfunction "SFDLED/GP1_14") (pintype "bidirectional"))
    )
    (net (code "94") (name "unconnected-(XA2-SPI_PHA{slash}GP6-Pad9)") (class "Default")
      (node (ref "XA2") (pin "9") (pinfunction "SPI_PHA/GP6_9") (pintype "bidirectional"))
    )
    (net (code "95") (name "unconnected-(XA2-SPI_POL{slash}GP5-Pad10)") (class "Default")
      (node (ref "XA2") (pin "10") (pinfunction "SPI_POL/GP5_10") (pintype "bidirectional"))
    )
    (net (code "96") (name "unconnected-(XA2-SYNC{slash}GP7-Pad4)") (class "Default")
      (node (ref "XA2") (pin "4") (pinfunction "SYNC/GP7_4") (pintype "bidirectional"))
    )
    (net (code "97") (name "unconnected-(XA2-TXLED{slash}GP3-Pad12)") (class "Default")
      (node (ref "XA2") (pin "12") (pinfunction "TXLED/GP3_12") (pintype "bidirectional"))
    )
    (net (code "98") (name "unconnected-(XA3-EXTON-Pad1)") (class "Default")
      (node (ref "XA3") (pin "1") (pinfunction "EXTON_1") (pintype "output"))
    )
    (net (code "99") (name "unconnected-(XA3-GP4-Pad11)") (class "Default")
      (node (ref "XA3") (pin "11") (pinfunction "GP4_11") (pintype "bidirectional"))
    )
    (net (code "100") (name "unconnected-(XA3-RXLED{slash}GP2-Pad13)") (class "Default")
      (node (ref "XA3") (pin "13") (pinfunction "RXLED/GP2_13") (pintype "bidirectional"))
    )
    (net (code "101") (name "unconnected-(XA3-RXOKLED{slash}GP0-Pad15)") (class "Default")
      (node (ref "XA3") (pin "15") (pinfunction "RXOKLED/GP0_15") (pintype "bidirectional"))
    )
    (net (code "102") (name "unconnected-(XA3-SFDLED{slash}GP1-Pad14)") (class "Default")
      (node (ref "XA3") (pin "14") (pinfunction "SFDLED/GP1_14") (pintype "bidirectional"))
    )
    (net (code "103") (name "unconnected-(XA3-SPI_PHA{slash}GP6-Pad9)") (class "Default")
      (node (ref "XA3") (pin "9") (pinfunction "SPI_PHA/GP6_9") (pintype "bidirectional"))
    )
    (net (code "104") (name "unconnected-(XA3-SPI_POL{slash}GP5-Pad10)") (class "Default")
      (node (ref "XA3") (pin "10") (pinfunction "SPI_POL/GP5_10") (pintype "bidirectional"))
    )
    (net (code "105") (name "unconnected-(XA3-SYNC{slash}GP7-Pad4)") (class "Default")
      (node (ref "XA3") (pin "4") (pinfunction "SYNC/GP7_4") (pintype "bidirectional"))
    )
    (net (code "106") (name "unconnected-(XA3-TXLED{slash}GP3-Pad12)") (class "Default")
      (node (ref "XA3") (pin "12") (pinfunction "TXLED/GP3_12") (pintype "bidirectional"))
    )
    (net (code "107") (name "unconnected-(XA4-P20-AP4_USB0_P-PadP20)") (class "Default")
      (node (ref "XA4") (pin "P20") (pinfunction "P20-AP4_USB0_P_P20") (pintype "bidirectional"))
    )
    (net (code "108") (name "unconnected-(XA4-P21-AP4_USB0_N-PadP21)") (class "Default")
      (node (ref "XA4") (pin "P21") (pinfunction "P21-AP4_USB0_N_P21") (pintype "bidirectional"))
    )
    (net (code "109") (name "unconnected-(XA4-P26-AP4_VDDUSB_0P9-PadP26)") (class "Default")
      (node (ref "XA4") (pin "P26") (pinfunction "P26-AP4_VDDUSB_0P9_P26") (pintype "bidirectional"))
    )
    (net (code "110") (name "unconnected-(XA4-P27-AP4-VDDUSB_3P3-PadP27)") (class "Default")
      (node (ref "XA4") (pin "P27") (pinfunction "P27-AP4-VDDUSB_3P3_P27") (pintype "bidirectional"))
    )
    (net (code "111") (name "unconnected-(XA4-P28_AP4_VDDMIPI_1P8-PadP28)") (class "Default")
      (node (ref "XA4") (pin "P28") (pinfunction "P28_AP4_VDDMIPI_1P8_P28") (pintype "bidirectional"))
    )
    (net (code "112") (name "unconnected-(XA4-P38-AP4_~{RESET}-PadP38)") (class "Default")
      (node (ref "XA4") (pin "P38") (pinfunction "P38-AP4_~{RESET}_P38") (pintype "bidirectional"))
    )
    (net (code "113") (name "~{CHG}") (class "Default")
      (node (ref "U3") (pin "8") (pinfunction "~{CHG}_8") (pintype "bidirectional"))
      (node (ref "U4") (pin "7") (pinfunction "~{CHG}_7") (pintype "bidirectional"))
      (node (ref "XA4") (pin "P2") (pinfunction "P2-AP4_GP58/TT_~{CHG}_P2") (pintype "bidirectional"))
    )
    (net (code "114") (name "~{DWM1_RST}") (class "Default")
      (node (ref "RX2") (pin "2") (pinfunction "2_2") (pintype "passive"))
      (node (ref "RX3") (pin "2") (pinfunction "2_2") (pintype "passive"))
      (node (ref "XA1") (pin "3") (pinfunction "~{RST}_3") (pintype "input"))
      (node (ref "XA4") (pin "P43") (pinfunction "P43-AP4_GP50/TT_~{DW_RESET}_P43") (pintype "bidirectional"))
    )
    (net (code "115") (name "~{DWM1_SPI_CS}") (class "Default")
      (node (ref "XA1") (pin "17") (pinfunction "~{SPI_CS}_17") (pintype "bidirectional"))
      (node (ref "XA4") (pin "P1") (pinfunction "P1-AP4_GP29/TT_~{DW_SPI_CS}_P1") (pintype "bidirectional"))
    )
    (net (code "116") (name "~{DWM2_RST}") (class "Default")
      (node (ref "RX2") (pin "1") (pinfunction "1_1") (pintype "passive"))
      (node (ref "RZ2") (pin "1") (pinfunction "1_1") (pintype "passive"))
      (node (ref "XA2") (pin "3") (pinfunction "~{RST}_3") (pintype "input"))
    )
    (net (code "117") (name "~{DWM2_SPI_CS}") (class "Default")
      (node (ref "XA2") (pin "17") (pinfunction "~{SPI_CS}_17") (pintype "bidirectional"))
      (node (ref "XA4") (pin "P8") (pinfunction "P8-AP4_GP24_P8") (pintype "bidirectional"))
    )
    (net (code "118") (name "~{DWM3_RST}") (class "Default")
      (node (ref "RX3") (pin "1") (pinfunction "1_1") (pintype "passive"))
      (node (ref "RZ3") (pin "1") (pinfunction "1_1") (pintype "passive"))
      (node (ref "XA3") (pin "3") (pinfunction "~{RST}_3") (pintype "input"))
    )
    (net (code "119") (name "~{DWM3_SPI_CS}") (class "Default")
      (node (ref "XA3") (pin "17") (pinfunction "~{SPI_CS}_17") (pintype "bidirectional"))
      (node (ref "XA4") (pin "P9") (pinfunction "P9-AP4_GP25_P9") (pintype "bidirectional"))
    )
    (net (code "120") (name "~{PG}") (class "Default")
      (node (ref "U3") (pin "5") (pinfunction "~{PG}_5") (pintype "bidirectional"))
      (node (ref "XA4") (pin "P3") (pinfunction "P3-AP4_GP60/TT_~{PG}_P3") (pintype "bidirectional"))
    )
  )
)
